# Codec_s.net
KiCad netlist of a schematic drawn in Altium Designer
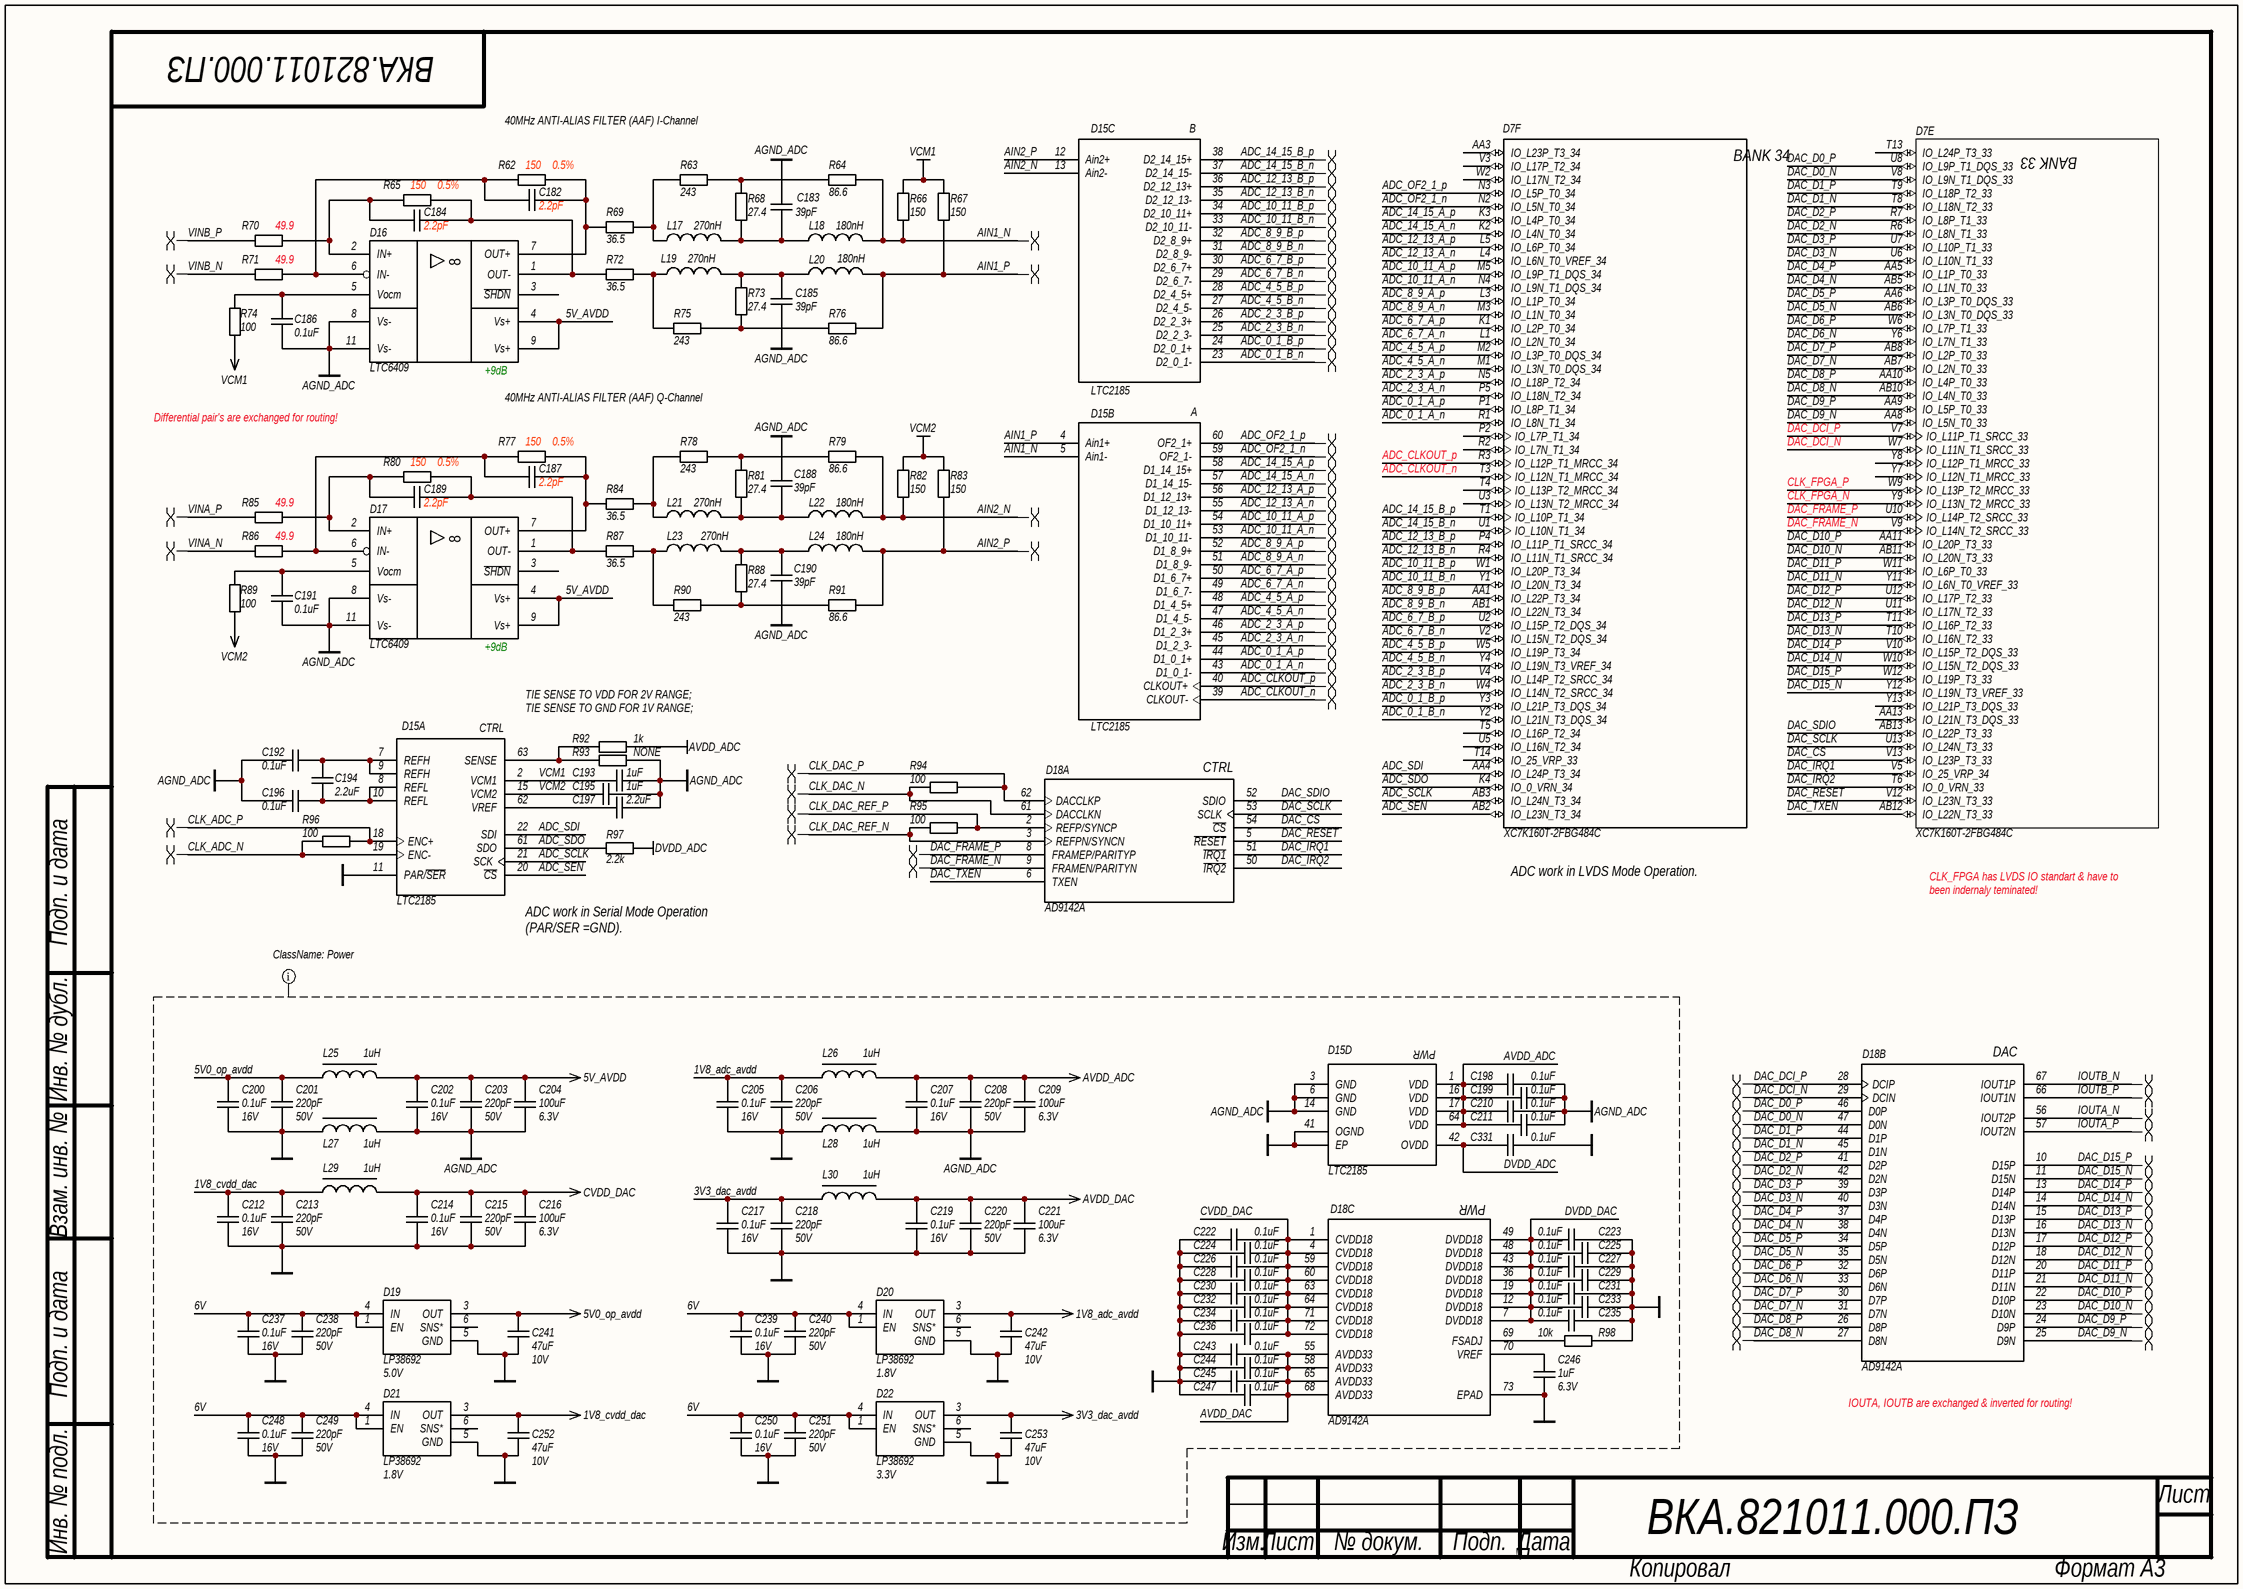
[diagram p0: Codec's.SchDoc]

(export (version "E")
  (design (tool "Eeschema 10.0.6"))
  (components
    (comp (ref "C182")
      (value "2.2pF")
      (footprint "C0402")
      (description "SMD Capacitor")
      (fields (field (name "MANUFACTURER") "Murata") (field (name "TOLERANCE") "0.1pF"))
      (libsource (lib "Kintex_SDR") (part "CAP"))
    )
    (comp (ref "C183")
      (value "39pF")
      (footprint "C0402")
      (description "SMD Capacitor")
      (fields (field (name "MANUFACTURER") "Murata") (field (name "TOLERANCE") "1%"))
      (libsource (lib "Kintex_SDR") (part "CAP"))
    )
    (comp (ref "C184")
      (value "2.2pF")
      (footprint "C0402")
      (description "SMD Capacitor")
      (fields (field (name "MANUFACTURER") "Murata") (field (name "TOLERANCE") "0.1pF"))
      (libsource (lib "Kintex_SDR") (part "CAP"))
    )
    (comp (ref "C185")
      (value "39pF")
      (footprint "C0402")
      (description "SMD Capacitor")
      (fields (field (name "MANUFACTURER") "Murata") (field (name "TOLERANCE") "1%"))
      (libsource (lib "Kintex_SDR") (part "CAP"))
    )
    (comp (ref "C186")
      (value "0.1uF")
      (footprint "C0402")
      (description "SMD Capacitor")
      (fields (field (name "MANUFACTURER") "Murata") (field (name "TOLERANCE") "10%"))
      (libsource (lib "Kintex_SDR") (part "CAP"))
    )
    (comp (ref "C187")
      (value "2.2pF")
      (footprint "C0402")
      (description "SMD Capacitor")
      (fields (field (name "MANUFACTURER") "Murata") (field (name "TOLERANCE") "0.1pF"))
      (libsource (lib "Kintex_SDR") (part "CAP"))
    )
    (comp (ref "C188")
      (value "39pF")
      (footprint "C0402")
      (description "SMD Capacitor")
      (fields (field (name "MANUFACTURER") "Murata") (field (name "TOLERANCE") "1%"))
      (libsource (lib "Kintex_SDR") (part "CAP"))
    )
    (comp (ref "C189")
      (value "2.2pF")
      (footprint "C0402")
      (description "SMD Capacitor")
      (fields (field (name "MANUFACTURER") "Murata") (field (name "TOLERANCE") "0.1pF"))
      (libsource (lib "Kintex_SDR") (part "CAP"))
    )
    (comp (ref "C190")
      (value "39pF")
      (footprint "C0402")
      (description "SMD Capacitor")
      (fields (field (name "MANUFACTURER") "Murata") (field (name "TOLERANCE") "1%"))
      (libsource (lib "Kintex_SDR") (part "CAP"))
    )
    (comp (ref "C191")
      (value "0.1uF")
      (footprint "C0402")
      (description "SMD Capacitor")
      (fields (field (name "MANUFACTURER") "Murata") (field (name "TOLERANCE") "10%"))
      (libsource (lib "Kintex_SDR") (part "CAP"))
    )
    (comp (ref "C192")
      (value "0.1uF")
      (footprint "C0402")
      (description "SMD Capacitor")
      (fields (field (name "MANUFACTURER") "Murata") (field (name "TOLERANCE") "10%"))
      (libsource (lib "Kintex_SDR") (part "CAP"))
    )
    (comp (ref "C193")
      (value "1uF")
      (footprint "C0402")
      (description "SMD Capacitor")
      (fields (field (name "MANUFACTURER") "Murata") (field (name "TOLERANCE") "10%"))
      (libsource (lib "Kintex_SDR") (part "CAP"))
    )
    (comp (ref "C194")
      (value "2.2uF")
      (footprint "C0603")
      (description "SMD Capacitor")
      (fields (field (name "MANUFACTURER") "Murata") (field (name "TOLERANCE") "10%"))
      (libsource (lib "Kintex_SDR") (part "CAP"))
    )
    (comp (ref "C195")
      (value "1uF")
      (footprint "C0402")
      (description "SMD Capacitor")
      (fields (field (name "MANUFACTURER") "Murata") (field (name "TOLERANCE") "10%"))
      (libsource (lib "Kintex_SDR") (part "CAP"))
    )
    (comp (ref "C196")
      (value "0.1uF")
      (footprint "C0402")
      (description "SMD Capacitor")
      (fields (field (name "MANUFACTURER") "Murata") (field (name "TOLERANCE") "10%"))
      (libsource (lib "Kintex_SDR") (part "CAP"))
    )
    (comp (ref "C197")
      (value "2.2uF")
      (footprint "C0603")
      (description "SMD Capacitor")
      (fields (field (name "MANUFACTURER") "Murata") (field (name "TOLERANCE") "10%"))
      (libsource (lib "Kintex_SDR") (part "CAP"))
    )
    (comp (ref "C198")
      (value "0.1uF")
      (footprint "C0402")
      (description "SMD Capacitor")
      (fields (field (name "MANUFACTURER") "Murata") (field (name "TOLERANCE") "10%"))
      (libsource (lib "Kintex_SDR") (part "CAP"))
    )
    (comp (ref "C199")
      (value "0.1uF")
      (footprint "C0402")
      (description "SMD Capacitor")
      (fields (field (name "MANUFACTURER") "Murata") (field (name "TOLERANCE") "10%"))
      (libsource (lib "Kintex_SDR") (part "CAP"))
    )
    (comp (ref "C200")
      (value "0.1uF")
      (footprint "C0603")
      (description "SMD Capacitor")
      (fields
        (field (name "MANUFACTURER") "Murata")
        (field (name "TOLERANCE") "10%")
        (field (name "VOLTAGE") "16V")
      )
      (libsource (lib "Kintex_SDR") (part "CAP"))
    )
    (comp (ref "C201")
      (value "220pF")
      (footprint "C0603")
      (description "SMD Capacitor")
      (fields
        (field (name "MANUFACTURER") "Murata")
        (field (name "TOLERANCE") "10%")
        (field (name "VOLTAGE") "50V")
      )
      (libsource (lib "Kintex_SDR") (part "CAP"))
    )
    (comp (ref "C202")
      (value "0.1uF")
      (footprint "C0603")
      (description "SMD Capacitor")
      (fields
        (field (name "MANUFACTURER") "Murata")
        (field (name "TOLERANCE") "10%")
        (field (name "VOLTAGE") "16V")
      )
      (libsource (lib "Kintex_SDR") (part "CAP"))
    )
    (comp (ref "C203")
      (value "220pF")
      (footprint "C0603")
      (description "SMD Capacitor")
      (fields
        (field (name "MANUFACTURER") "Murata")
        (field (name "TOLERANCE") "10%")
        (field (name "VOLTAGE") "50V")
      )
      (libsource (lib "Kintex_SDR") (part "CAP"))
    )
    (comp (ref "C204")
      (value "100uF")
      (footprint "C1210")
      (description "SMD Capacitor")
      (fields
        (field (name "MANUFACTURER") "Murata")
        (field (name "TOLERANCE") "20%")
        (field (name "VOLTAGE") "6.3V")
      )
      (libsource (lib "Kintex_SDR") (part "CAP uF"))
    )
    (comp (ref "C205")
      (value "0.1uF")
      (footprint "C0603")
      (description "SMD Capacitor")
      (fields
        (field (name "MANUFACTURER") "Murata")
        (field (name "TOLERANCE") "10%")
        (field (name "VOLTAGE") "16V")
      )
      (libsource (lib "Kintex_SDR") (part "CAP"))
    )
    (comp (ref "C206")
      (value "220pF")
      (footprint "C0603")
      (description "SMD Capacitor")
      (fields
        (field (name "MANUFACTURER") "Murata")
        (field (name "TOLERANCE") "10%")
        (field (name "VOLTAGE") "50V")
      )
      (libsource (lib "Kintex_SDR") (part "CAP"))
    )
    (comp (ref "C207")
      (value "0.1uF")
      (footprint "C0603")
      (description "SMD Capacitor")
      (fields
        (field (name "MANUFACTURER") "Murata")
        (field (name "TOLERANCE") "10%")
        (field (name "VOLTAGE") "16V")
      )
      (libsource (lib "Kintex_SDR") (part "CAP"))
    )
    (comp (ref "C208")
      (value "220pF")
      (footprint "C0603")
      (description "SMD Capacitor")
      (fields
        (field (name "MANUFACTURER") "Murata")
        (field (name "TOLERANCE") "10%")
        (field (name "VOLTAGE") "50V")
      )
      (libsource (lib "Kintex_SDR") (part "CAP"))
    )
    (comp (ref "C209")
      (value "100uF")
      (footprint "C1210")
      (description "SMD Capacitor")
      (fields
        (field (name "MANUFACTURER") "Murata")
        (field (name "TOLERANCE") "20%")
        (field (name "VOLTAGE") "6.3V")
      )
      (libsource (lib "Kintex_SDR") (part "CAP uF"))
    )
    (comp (ref "C210")
      (value "0.1uF")
      (footprint "C0402")
      (description "SMD Capacitor")
      (fields (field (name "MANUFACTURER") "Murata") (field (name "TOLERANCE") "10%"))
      (libsource (lib "Kintex_SDR") (part "CAP"))
    )
    (comp (ref "C211")
      (value "0.1uF")
      (footprint "C0402")
      (description "SMD Capacitor")
      (fields (field (name "MANUFACTURER") "Murata") (field (name "TOLERANCE") "10%"))
      (libsource (lib "Kintex_SDR") (part "CAP"))
    )
    (comp (ref "C212")
      (value "0.1uF")
      (footprint "C0603")
      (description "SMD Capacitor")
      (fields
        (field (name "MANUFACTURER") "Murata")
        (field (name "TOLERANCE") "10%")
        (field (name "VOLTAGE") "16V")
      )
      (libsource (lib "Kintex_SDR") (part "CAP"))
    )
    (comp (ref "C213")
      (value "220pF")
      (footprint "C0603")
      (description "SMD Capacitor")
      (fields
        (field (name "MANUFACTURER") "Murata")
        (field (name "TOLERANCE") "10%")
        (field (name "VOLTAGE") "50V")
      )
      (libsource (lib "Kintex_SDR") (part "CAP"))
    )
    (comp (ref "C214")
      (value "0.1uF")
      (footprint "C0603")
      (description "SMD Capacitor")
      (fields
        (field (name "MANUFACTURER") "Murata")
        (field (name "TOLERANCE") "10%")
        (field (name "VOLTAGE") "16V")
      )
      (libsource (lib "Kintex_SDR") (part "CAP"))
    )
    (comp (ref "C215")
      (value "220pF")
      (footprint "C0603")
      (description "SMD Capacitor")
      (fields
        (field (name "MANUFACTURER") "Murata")
        (field (name "TOLERANCE") "10%")
        (field (name "VOLTAGE") "50V")
      )
      (libsource (lib "Kintex_SDR") (part "CAP"))
    )
    (comp (ref "C216")
      (value "100uF")
      (footprint "C1210")
      (description "SMD Capacitor")
      (fields
        (field (name "MANUFACTURER") "Murata")
        (field (name "TOLERANCE") "20%")
        (field (name "VOLTAGE") "6.3V")
      )
      (libsource (lib "Kintex_SDR") (part "CAP uF"))
    )
    (comp (ref "C217")
      (value "0.1uF")
      (footprint "C0603")
      (description "SMD Capacitor")
      (fields
        (field (name "MANUFACTURER") "Murata")
        (field (name "TOLERANCE") "10%")
        (field (name "VOLTAGE") "16V")
      )
      (libsource (lib "Kintex_SDR") (part "CAP"))
    )
    (comp (ref "C218")
      (value "220pF")
      (footprint "C0603")
      (description "SMD Capacitor")
      (fields
        (field (name "MANUFACTURER") "Murata")
        (field (name "TOLERANCE") "10%")
        (field (name "VOLTAGE") "50V")
      )
      (libsource (lib "Kintex_SDR") (part "CAP"))
    )
    (comp (ref "C219")
      (value "0.1uF")
      (footprint "C0603")
      (description "SMD Capacitor")
      (fields
        (field (name "MANUFACTURER") "Murata")
        (field (name "TOLERANCE") "10%")
        (field (name "VOLTAGE") "16V")
      )
      (libsource (lib "Kintex_SDR") (part "CAP"))
    )
    (comp (ref "C220")
      (value "220pF")
      (footprint "C0603")
      (description "SMD Capacitor")
      (fields
        (field (name "MANUFACTURER") "Murata")
        (field (name "TOLERANCE") "10%")
        (field (name "VOLTAGE") "50V")
      )
      (libsource (lib "Kintex_SDR") (part "CAP"))
    )
    (comp (ref "C221")
      (value "100uF")
      (footprint "C1210")
      (description "SMD Capacitor")
      (fields
        (field (name "MANUFACTURER") "Murata")
        (field (name "TOLERANCE") "20%")
        (field (name "VOLTAGE") "6.3V")
      )
      (libsource (lib "Kintex_SDR") (part "CAP uF"))
    )
    (comp (ref "C222")
      (value "0.1uF")
      (footprint "C0402")
      (description "SMD Capacitor")
      (fields (field (name "MANUFACTURER") "Murata") (field (name "TOLERANCE") "10%"))
      (libsource (lib "Kintex_SDR") (part "CAP"))
    )
    (comp (ref "C223")
      (value "0.1uF")
      (footprint "C0402")
      (description "SMD Capacitor")
      (fields (field (name "MANUFACTURER") "Murata") (field (name "TOLERANCE") "10%"))
      (libsource (lib "Kintex_SDR") (part "CAP"))
    )
    (comp (ref "C224")
      (value "0.1uF")
      (footprint "C0402")
      (description "SMD Capacitor")
      (fields (field (name "MANUFACTURER") "Murata") (field (name "TOLERANCE") "10%"))
      (libsource (lib "Kintex_SDR") (part "CAP"))
    )
    (comp (ref "C225")
      (value "0.1uF")
      (footprint "C0402")
      (description "SMD Capacitor")
      (fields (field (name "MANUFACTURER") "Murata") (field (name "TOLERANCE") "10%"))
      (libsource (lib "Kintex_SDR") (part "CAP"))
    )
    (comp (ref "C226")
      (value "0.1uF")
      (footprint "C0402")
      (description "SMD Capacitor")
      (fields (field (name "MANUFACTURER") "Murata") (field (name "TOLERANCE") "10%"))
      (libsource (lib "Kintex_SDR") (part "CAP"))
    )
    (comp (ref "C227")
      (value "0.1uF")
      (footprint "C0402")
      (description "SMD Capacitor")
      (fields (field (name "MANUFACTURER") "Murata") (field (name "TOLERANCE") "10%"))
      (libsource (lib "Kintex_SDR") (part "CAP"))
    )
    (comp (ref "C228")
      (value "0.1uF")
      (footprint "C0402")
      (description "SMD Capacitor")
      (fields (field (name "MANUFACTURER") "Murata") (field (name "TOLERANCE") "10%"))
      (libsource (lib "Kintex_SDR") (part "CAP"))
    )
    (comp (ref "C229")
      (value "0.1uF")
      (footprint "C0402")
      (description "SMD Capacitor")
      (fields (field (name "MANUFACTURER") "Murata") (field (name "TOLERANCE") "10%"))
      (libsource (lib "Kintex_SDR") (part "CAP"))
    )
    (comp (ref "C230")
      (value "0.1uF")
      (footprint "C0402")
      (description "SMD Capacitor")
      (fields (field (name "MANUFACTURER") "Murata") (field (name "TOLERANCE") "10%"))
      (libsource (lib "Kintex_SDR") (part "CAP"))
    )
    (comp (ref "C231")
      (value "0.1uF")
      (footprint "C0402")
      (description "SMD Capacitor")
      (fields (field (name "MANUFACTURER") "Murata") (field (name "TOLERANCE") "10%"))
      (libsource (lib "Kintex_SDR") (part "CAP"))
    )
    (comp (ref "C232")
      (value "0.1uF")
      (footprint "C0402")
      (description "SMD Capacitor")
      (fields (field (name "MANUFACTURER") "Murata") (field (name "TOLERANCE") "10%"))
      (libsource (lib "Kintex_SDR") (part "CAP"))
    )
    (comp (ref "C233")
      (value "0.1uF")
      (footprint "C0402")
      (description "SMD Capacitor")
      (fields (field (name "MANUFACTURER") "Murata") (field (name "TOLERANCE") "10%"))
      (libsource (lib "Kintex_SDR") (part "CAP"))
    )
    (comp (ref "C234")
      (value "0.1uF")
      (footprint "C0402")
      (description "SMD Capacitor")
      (fields (field (name "MANUFACTURER") "Murata") (field (name "TOLERANCE") "10%"))
      (libsource (lib "Kintex_SDR") (part "CAP"))
    )
    (comp (ref "C235")
      (value "0.1uF")
      (footprint "C0402")
      (description "SMD Capacitor")
      (fields (field (name "MANUFACTURER") "Murata") (field (name "TOLERANCE") "10%"))
      (libsource (lib "Kintex_SDR") (part "CAP"))
    )
    (comp (ref "C236")
      (value "0.1uF")
      (footprint "C0402")
      (description "SMD Capacitor")
      (fields (field (name "MANUFACTURER") "Murata") (field (name "TOLERANCE") "10%"))
      (libsource (lib "Kintex_SDR") (part "CAP"))
    )
    (comp (ref "C237")
      (value "0.1uF")
      (footprint "C0603")
      (description "SMD Capacitor")
      (fields
        (field (name "MANUFACTURER") "Murata")
        (field (name "TOLERANCE") "10%")
        (field (name "VOLTAGE") "16V")
      )
      (libsource (lib "Kintex_SDR") (part "CAP"))
    )
    (comp (ref "C238")
      (value "220pF")
      (footprint "C0603")
      (description "SMD Capacitor")
      (fields
        (field (name "MANUFACTURER") "Murata")
        (field (name "TOLERANCE") "10%")
        (field (name "VOLTAGE") "50V")
      )
      (libsource (lib "Kintex_SDR") (part "CAP"))
    )
    (comp (ref "C239")
      (value "0.1uF")
      (footprint "C0603")
      (description "SMD Capacitor")
      (fields
        (field (name "MANUFACTURER") "Murata")
        (field (name "TOLERANCE") "10%")
        (field (name "VOLTAGE") "16V")
      )
      (libsource (lib "Kintex_SDR") (part "CAP"))
    )
    (comp (ref "C240")
      (value "220pF")
      (footprint "C0603")
      (description "SMD Capacitor")
      (fields
        (field (name "MANUFACTURER") "Murata")
        (field (name "TOLERANCE") "10%")
        (field (name "VOLTAGE") "50V")
      )
      (libsource (lib "Kintex_SDR") (part "CAP"))
    )
    (comp (ref "C241")
      (value "47uF")
      (footprint "C1210")
      (description "SMD Capacitor")
      (fields
        (field (name "MANUFACTURER") "Murata")
        (field (name "TOLERANCE") "10%")
        (field (name "VOLTAGE") "10V")
      )
      (libsource (lib "Kintex_SDR") (part "CAP uF"))
    )
    (comp (ref "C242")
      (value "47uF")
      (footprint "C1210")
      (description "SMD Capacitor")
      (fields
        (field (name "MANUFACTURER") "Murata")
        (field (name "TOLERANCE") "10%")
        (field (name "VOLTAGE") "10V")
      )
      (libsource (lib "Kintex_SDR") (part "CAP uF"))
    )
    (comp (ref "C243")
      (value "0.1uF")
      (footprint "C0402")
      (description "SMD Capacitor")
      (fields (field (name "MANUFACTURER") "Murata") (field (name "TOLERANCE") "10%"))
      (libsource (lib "Kintex_SDR") (part "CAP"))
    )
    (comp (ref "C244")
      (value "0.1uF")
      (footprint "C0402")
      (description "SMD Capacitor")
      (fields (field (name "MANUFACTURER") "Murata") (field (name "TOLERANCE") "10%"))
      (libsource (lib "Kintex_SDR") (part "CAP"))
    )
    (comp (ref "C245")
      (value "0.1uF")
      (footprint "C0402")
      (description "SMD Capacitor")
      (fields (field (name "MANUFACTURER") "Murata") (field (name "TOLERANCE") "10%"))
      (libsource (lib "Kintex_SDR") (part "CAP"))
    )
    (comp (ref "C246")
      (value "1uF")
      (footprint "C0402")
      (description "SMD Capacitor")
      (fields
        (field (name "MANUFACTURER") "Murata")
        (field (name "TOLERANCE") "10%")
        (field (name "VOLTAGE") "6.3V")
      )
      (libsource (lib "Kintex_SDR") (part "CAP"))
    )
    (comp (ref "C247")
      (value "0.1uF")
      (footprint "C0402")
      (description "SMD Capacitor")
      (fields (field (name "MANUFACTURER") "Murata") (field (name "TOLERANCE") "10%"))
      (libsource (lib "Kintex_SDR") (part "CAP"))
    )
    (comp (ref "C248")
      (value "0.1uF")
      (footprint "C0603")
      (description "SMD Capacitor")
      (fields
        (field (name "MANUFACTURER") "Murata")
        (field (name "TOLERANCE") "10%")
        (field (name "VOLTAGE") "16V")
      )
      (libsource (lib "Kintex_SDR") (part "CAP"))
    )
    (comp (ref "C249")
      (value "220pF")
      (footprint "C0603")
      (description "SMD Capacitor")
      (fields
        (field (name "MANUFACTURER") "Murata")
        (field (name "TOLERANCE") "10%")
        (field (name "VOLTAGE") "50V")
      )
      (libsource (lib "Kintex_SDR") (part "CAP"))
    )
    (comp (ref "C250")
      (value "0.1uF")
      (footprint "C0603")
      (description "SMD Capacitor")
      (fields
        (field (name "MANUFACTURER") "Murata")
        (field (name "TOLERANCE") "10%")
        (field (name "VOLTAGE") "16V")
      )
      (libsource (lib "Kintex_SDR") (part "CAP"))
    )
    (comp (ref "C251")
      (value "220pF")
      (footprint "C0603")
      (description "SMD Capacitor")
      (fields
        (field (name "MANUFACTURER") "Murata")
        (field (name "TOLERANCE") "10%")
        (field (name "VOLTAGE") "50V")
      )
      (libsource (lib "Kintex_SDR") (part "CAP"))
    )
    (comp (ref "C252")
      (value "47uF")
      (footprint "C1210")
      (description "SMD Capacitor")
      (fields
        (field (name "MANUFACTURER") "Murata")
        (field (name "TOLERANCE") "10%")
        (field (name "VOLTAGE") "10V")
      )
      (libsource (lib "Kintex_SDR") (part "CAP uF"))
    )
    (comp (ref "C253")
      (value "47uF")
      (footprint "C1210")
      (description "SMD Capacitor")
      (fields
        (field (name "MANUFACTURER") "Murata")
        (field (name "TOLERANCE") "10%")
        (field (name "VOLTAGE") "10V")
      )
      (libsource (lib "Kintex_SDR") (part "CAP uF"))
    )
    (comp (ref "C331")
      (value "0.1uF")
      (footprint "C0402")
      (description "SMD Capacitor")
      (fields (field (name "MANUFACTURER") "Murata") (field (name "TOLERANCE") "10%"))
      (libsource (lib "Kintex_SDR") (part "CAP"))
    )
    (comp (ref "D7")
      (value "XC7K160T-2FBG484C")
      (footprint "FBG484")
      (description "Xilinx 7-Series FPGA")
      (fields (field (name "MANUFACTURER") "Xilinx"))
      (libsource (lib "Kintex_SDR") (part "XC7K160T-2FBG484C"))
    )
    (comp (ref "D15")
      (value "LTC2185")
      (footprint "QFN-64")
      (description "Dual 16-Bit, 125Msps  Low Power 3V ADC")
      (fields (field (name "VOLTAGE") "Single 1.8V Supply"))
      (libsource (lib "Kintex_SDR") (part "LTC2185"))
    )
    (comp (ref "D16")
      (value "LTC6409")
      (footprint "QFN-10")
      (description "Differential Amplifier/ADC   Driver")
      (fields (field (name "MANUFACTURER") "Linear Technology") (field (name "VOLTAGE") "2.7V to 5.25V"))
      (libsource (lib "Kintex_SDR") (part "LTC6409"))
    )
    (comp (ref "D17")
      (value "LTC6409")
      (footprint "QFN-10")
      (description "Differential Amplifier/ADC   Driver")
      (fields (field (name "MANUFACTURER") "Linear Technology") (field (name "VOLTAGE") "2.7V to 5.25V"))
      (libsource (lib "Kintex_SDR") (part "LTC6409"))
    )
    (comp (ref "D18")
      (value "AD9142A")
      (footprint "LFCSP_VQ-72")
      (description "Dual, 16-Bit, 1600 MSPS, TxDAC+   Digital-to-Analog Converter")
      (fields (field (name "VOLTAGE") "3.3V, 1.8V"))
      (libsource (lib "Kintex_SDR") (part "AD9142A"))
    )
    (comp (ref "D19")
      (value "LP38692")
      (footprint "SOT-223-5")
      (description "Linear Regulator")
      (fields (field (name "VOLTAGE") "5.0V"))
      (libsource (lib "Kintex_SDR") (part "LP38692"))
    )
    (comp (ref "D20")
      (value "LP38692")
      (footprint "SOT-223-5")
      (description "Linear Regulator")
      (fields (field (name "VOLTAGE") "1.8V"))
      (libsource (lib "Kintex_SDR") (part "LP38692"))
    )
    (comp (ref "D21")
      (value "LP38692")
      (footprint "SOT-223-5")
      (description "Linear Regulator")
      (fields (field (name "VOLTAGE") "1.8V"))
      (libsource (lib "Kintex_SDR") (part "LP38692"))
    )
    (comp (ref "D22")
      (value "LP38692")
      (footprint "SOT-223-5")
      (description "Linear Regulator")
      (fields (field (name "VOLTAGE") "3.3V"))
      (libsource (lib "Kintex_SDR") (part "LP38692"))
    )
    (comp (ref "L17")
      (value "270nH")
      (footprint "L0603")
      (description "Chip SMD Inductor")
      (fields (field (name "MANUFACTURER") "Murata") (field (name "TOLERANCE") "±2%"))
      (libsource (lib "Kintex_SDR") (part "Inductor RF"))
    )
    (comp (ref "L18")
      (value "180nH")
      (footprint "L0603")
      (description "Chip SMD Inductor")
      (fields (field (name "MANUFACTURER") "Murata") (field (name "TOLERANCE") "±2%"))
      (libsource (lib "Kintex_SDR") (part "Inductor RF"))
    )
    (comp (ref "L19")
      (value "270nH")
      (footprint "L0603")
      (description "Chip SMD Inductor")
      (fields (field (name "MANUFACTURER") "Murata") (field (name "TOLERANCE") "±2%"))
      (libsource (lib "Kintex_SDR") (part "Inductor RF"))
    )
    (comp (ref "L20")
      (value "180nH")
      (footprint "L0603")
      (description "Chip SMD Inductor")
      (fields (field (name "MANUFACTURER") "Murata") (field (name "TOLERANCE") "±2%"))
      (libsource (lib "Kintex_SDR") (part "Inductor RF"))
    )
    (comp (ref "L21")
      (value "270nH")
      (footprint "L0603")
      (description "Chip SMD Inductor")
      (fields (field (name "MANUFACTURER") "Murata") (field (name "TOLERANCE") "±2%"))
      (libsource (lib "Kintex_SDR") (part "Inductor RF"))
    )
    (comp (ref "L22")
      (value "180nH")
      (footprint "L0603")
      (description "Chip SMD Inductor")
      (fields (field (name "MANUFACTURER") "Murata") (field (name "TOLERANCE") "±2%"))
      (libsource (lib "Kintex_SDR") (part "Inductor RF"))
    )
    (comp (ref "L23")
      (value "270nH")
      (footprint "L0603")
      (description "Chip SMD Inductor")
      (fields (field (name "MANUFACTURER") "Murata") (field (name "TOLERANCE") "±2%"))
      (libsource (lib "Kintex_SDR") (part "Inductor RF"))
    )
    (comp (ref "L24")
      (value "180nH")
      (footprint "L0603")
      (description "Chip SMD Inductor")
      (fields (field (name "MANUFACTURER") "Murata") (field (name "TOLERANCE") "±2%"))
      (libsource (lib "Kintex_SDR") (part "Inductor RF"))
    )
    (comp (ref "L25")
      (value "1uH")
      (footprint "L1210_Murata")
      (description "Inductor Power Lines")
      (fields (field (name "MANUFACTURER") "Murata") (field (name "TOLERANCE") "5%"))
      (libsource (lib "Kintex_SDR") (part "Inductor LF"))
    )
    (comp (ref "L26")
      (value "1uH")
      (footprint "L1210_Murata")
      (description "Inductor Power Lines")
      (fields (field (name "MANUFACTURER") "Murata") (field (name "TOLERANCE") "5%"))
      (libsource (lib "Kintex_SDR") (part "Inductor LF"))
    )
    (comp (ref "L27")
      (value "1uH")
      (footprint "L1210_Murata")
      (description "Inductor Power Lines")
      (fields (field (name "MANUFACTURER") "Murata") (field (name "TOLERANCE") "5%"))
      (libsource (lib "Kintex_SDR") (part "Inductor LF"))
    )
    (comp (ref "L28")
      (value "1uH")
      (footprint "L1210_Murata")
      (description "Inductor Power Lines")
      (fields (field (name "MANUFACTURER") "Murata") (field (name "TOLERANCE") "5%"))
      (libsource (lib "Kintex_SDR") (part "Inductor LF"))
    )
    (comp (ref "L29")
      (value "1uH")
      (footprint "L1210_Murata")
      (description "Inductor Power Lines")
      (fields (field (name "MANUFACTURER") "Murata") (field (name "TOLERANCE") "5%"))
      (libsource (lib "Kintex_SDR") (part "Inductor LF"))
    )
    (comp (ref "L30")
      (value "1uH")
      (footprint "L1210_Murata")
      (description "Inductor Power Lines")
      (fields (field (name "MANUFACTURER") "Murata") (field (name "TOLERANCE") "5%"))
      (libsource (lib "Kintex_SDR") (part "Inductor LF"))
    )
    (comp (ref "R62")
      (value "150")
      (footprint "R0402")
      (description "SMD Resistor")
      (fields
        (field (name "POWER") "0.062 Wt")
        (field (name "TOLERANCE") "0.5%")
        (field (name "MANUFACTURER") "Panasonic Electronic Components")
      )
      (libsource (lib "Kintex_SDR") (part "RES"))
    )
    (comp (ref "R63")
      (value "243")
      (footprint "R0402")
      (description "SMD Resistor")
      (fields (field (name "POWER") "0.062 Wt") (field (name "TOLERANCE") "1%"))
      (libsource (lib "Kintex_SDR") (part "RES"))
    )
    (comp (ref "R64")
      (value "86.6")
      (footprint "R0402")
      (description "SMD Resistor")
      (fields (field (name "POWER") "0.062 Wt") (field (name "TOLERANCE") "1%"))
      (libsource (lib "Kintex_SDR") (part "RES"))
    )
    (comp (ref "R65")
      (value "150")
      (footprint "R0402")
      (description "SMD Resistor")
      (fields
        (field (name "POWER") "0.062 Wt")
        (field (name "TOLERANCE") "0.5%")
        (field (name "MANUFACTURER") "Panasonic Electronic Components")
      )
      (libsource (lib "Kintex_SDR") (part "RES"))
    )
    (comp (ref "R66")
      (value "150")
      (footprint "R0402")
      (description "SMD Resistor")
      (fields (field (name "POWER") "0.062 Wt") (field (name "TOLERANCE") "1%"))
      (libsource (lib "Kintex_SDR") (part "RES"))
    )
    (comp (ref "R67")
      (value "150")
      (footprint "R0402")
      (description "SMD Resistor")
      (fields (field (name "POWER") "0.062 Wt") (field (name "TOLERANCE") "1%"))
      (libsource (lib "") (part "RES_1"))
    )
    (comp (ref "R68")
      (value "27.4")
      (footprint "R0402")
      (description "SMD Resistor")
      (fields (field (name "POWER") "0.062 Wt") (field (name "TOLERANCE") "1%"))
      (libsource (lib "") (part "RES_2"))
    )
    (comp (ref "R69")
      (value "36.5")
      (footprint "R0402")
      (description "SMD Resistor")
      (fields (field (name "POWER") "0.062 Wt") (field (name "TOLERANCE") "1%"))
      (libsource (lib "") (part "RES_1"))
    )
    (comp (ref "R70")
      (value "49.9")
      (footprint "R0402")
      (description "SMD Resistor")
      (fields (field (name "POWER") "0.063 Wt") (field (name "TOLERANCE") "0.5%"))
      (libsource (lib "") (part "RES_1"))
    )
    (comp (ref "R71")
      (value "49.9")
      (footprint "R0402")
      (description "SMD Resistor")
      (fields (field (name "POWER") "0.063 Wt") (field (name "TOLERANCE") "0.5%"))
      (libsource (lib "") (part "RES_1"))
    )
    (comp (ref "R72")
      (value "36.5")
      (footprint "R0402")
      (description "SMD Resistor")
      (fields (field (name "POWER") "0.062 Wt") (field (name "TOLERANCE") "1%"))
      (libsource (lib "") (part "RES_1"))
    )
    (comp (ref "R73")
      (value "27.4")
      (footprint "R0402")
      (description "SMD Resistor")
      (fields (field (name "POWER") "0.062 Wt") (field (name "TOLERANCE") "1%"))
      (libsource (lib "") (part "RES_2"))
    )
    (comp (ref "R74")
      (value "100")
      (footprint "R0402")
      (description "SMD Resistor")
      (fields (field (name "POWER") "0.062 Wt") (field (name "TOLERANCE") "5%"))
      (libsource (lib "") (part "RES_1"))
    )
    (comp (ref "R75")
      (value "243")
      (footprint "R0402")
      (description "SMD Resistor")
      (fields (field (name "POWER") "0.062 Wt") (field (name "TOLERANCE") "1%"))
      (libsource (lib "Kintex_SDR") (part "RES"))
    )
    (comp (ref "R76")
      (value "86.6")
      (footprint "R0402")
      (description "SMD Resistor")
      (fields (field (name "POWER") "0.062 Wt") (field (name "TOLERANCE") "1%"))
      (libsource (lib "Kintex_SDR") (part "RES"))
    )
    (comp (ref "R77")
      (value "150")
      (footprint "R0402")
      (description "SMD Resistor")
      (fields
        (field (name "POWER") "0.062 Wt")
        (field (name "TOLERANCE") "0.5%")
        (field (name "MANUFACTURER") "Panasonic Electronic Components")
      )
      (libsource (lib "Kintex_SDR") (part "RES"))
    )
    (comp (ref "R78")
      (value "243")
      (footprint "R0402")
      (description "SMD Resistor")
      (fields (field (name "POWER") "0.062 Wt") (field (name "TOLERANCE") "1%"))
      (libsource (lib "Kintex_SDR") (part "RES"))
    )
    (comp (ref "R79")
      (value "86.6")
      (footprint "R0402")
      (description "SMD Resistor")
      (fields (field (name "POWER") "0.062 Wt") (field (name "TOLERANCE") "1%"))
      (libsource (lib "Kintex_SDR") (part "RES"))
    )
    (comp (ref "R80")
      (value "150")
      (footprint "R0402")
      (description "SMD Resistor")
      (fields
        (field (name "POWER") "0.062 Wt")
        (field (name "TOLERANCE") "0.5%")
        (field (name "MANUFACTURER") "Panasonic Electronic Components")
      )
      (libsource (lib "Kintex_SDR") (part "RES"))
    )
    (comp (ref "R81")
      (value "27.4")
      (footprint "R0402")
      (description "SMD Resistor")
      (fields (field (name "POWER") "0.062 Wt") (field (name "TOLERANCE") "1%"))
      (libsource (lib "") (part "RES_2"))
    )
    (comp (ref "R82")
      (value "150")
      (footprint "R0402")
      (description "SMD Resistor")
      (fields (field (name "POWER") "0.062 Wt") (field (name "TOLERANCE") "1%"))
      (libsource (lib "") (part "RES_2"))
    )
    (comp (ref "R83")
      (value "150")
      (footprint "R0402")
      (description "SMD Resistor")
      (fields (field (name "POWER") "0.062 Wt") (field (name "TOLERANCE") "1%"))
      (libsource (lib "") (part "RES_2"))
    )
    (comp (ref "R84")
      (value "36.5")
      (footprint "R0402")
      (description "SMD Resistor")
      (fields (field (name "POWER") "0.062 Wt") (field (name "TOLERANCE") "1%"))
      (libsource (lib "") (part "RES_1"))
    )
    (comp (ref "R85")
      (value "49.9")
      (footprint "R0402")
      (description "SMD Resistor")
      (fields (field (name "POWER") "0.063 Wt") (field (name "TOLERANCE") "0.5%"))
      (libsource (lib "") (part "RES_1"))
    )
    (comp (ref "R86")
      (value "49.9")
      (footprint "R0402")
      (description "SMD Resistor")
      (fields (field (name "POWER") "0.063 Wt") (field (name "TOLERANCE") "0.5%"))
      (libsource (lib "") (part "RES_1"))
    )
    (comp (ref "R87")
      (value "36.5")
      (footprint "R0402")
      (description "SMD Resistor")
      (fields (field (name "POWER") "0.062 Wt") (field (name "TOLERANCE") "1%"))
      (libsource (lib "") (part "RES_1"))
    )
    (comp (ref "R88")
      (value "27.4")
      (footprint "R0402")
      (description "SMD Resistor")
      (fields (field (name "POWER") "0.062 Wt") (field (name "TOLERANCE") "1%"))
      (libsource (lib "") (part "RES_2"))
    )
    (comp (ref "R89")
      (value "100")
      (footprint "R0402")
      (description "SMD Resistor")
      (fields (field (name "POWER") "0.062 Wt") (field (name "TOLERANCE") "5%"))
      (libsource (lib "") (part "RES_1"))
    )
    (comp (ref "R90")
      (value "243")
      (footprint "R0402")
      (description "SMD Resistor")
      (fields (field (name "POWER") "0.062 Wt") (field (name "TOLERANCE") "1%"))
      (libsource (lib "Kintex_SDR") (part "RES"))
    )
    (comp (ref "R91")
      (value "86.6")
      (footprint "R0402")
      (description "SMD Resistor")
      (fields (field (name "POWER") "0.062 Wt") (field (name "TOLERANCE") "1%"))
      (libsource (lib "Kintex_SDR") (part "RES"))
    )
    (comp (ref "R92")
      (value "1k")
      (footprint "R0402")
      (description "SMD Resistor")
      (fields (field (name "POWER") "0.062 Wt") (field (name "TOLERANCE") "5%"))
      (libsource (lib "Kintex_SDR") (part "RES"))
    )
    (comp (ref "R93")
      (value "NONE")
      (footprint "R0402")
      (description "SMD Resistor")
      (fields
        (field (name "POWER") "0.062 Wt")
        (field (name "MANUFACTURER") "Panasonic Electronic Components")
      )
      (libsource (lib "Kintex_SDR") (part "RES"))
    )
    (comp (ref "R94")
      (value "100")
      (footprint "R0402")
      (description "SMD Resistor")
      (fields (field (name "POWER") "0.062 Wt") (field (name "TOLERANCE") "5%"))
      (libsource (lib "Kintex_SDR") (part "RES"))
    )
    (comp (ref "R95")
      (value "100")
      (footprint "R0402")
      (description "SMD Resistor")
      (fields (field (name "POWER") "0.062 Wt") (field (name "TOLERANCE") "5%"))
      (libsource (lib "Kintex_SDR") (part "RES"))
    )
    (comp (ref "R96")
      (value "100")
      (footprint "R0402")
      (description "SMD Resistor")
      (fields (field (name "POWER") "0.062 Wt") (field (name "TOLERANCE") "5%"))
      (libsource (lib "Kintex_SDR") (part "RES"))
    )
    (comp (ref "R97")
      (value "2.2k")
      (footprint "R0402")
      (description "SMD Resistor")
      (fields (field (name "POWER") "0.062 Wt") (field (name "TOLERANCE") "5%"))
      (libsource (lib "") (part "RES_1"))
    )
    (comp (ref "R98")
      (value "10k")
      (footprint "R0402")
      (description "SMD Resistor")
      (fields (field (name "POWER") "0.062 Wt") (field (name "TOLERANCE") "5%"))
      (libsource (lib "Kintex_SDR") (part "RES"))
    )
  )
  (nets
    (net (code "1") (name "/6V") (class "Default")
      (node (ref "C237") (pin "2") (pinfunction "2_2") (pintype "passive"))
      (node (ref "C238") (pin "2") (pinfunction "2_2") (pintype "passive"))
      (node (ref "C239") (pin "2") (pinfunction "2_2") (pintype "passive"))
      (node (ref "C240") (pin "2") (pinfunction "2_2") (pintype "passive"))
      (node (ref "C248") (pin "2") (pinfunction "2_2") (pintype "passive"))
      (node (ref "C249") (pin "2") (pinfunction "2_2") (pintype "passive"))
      (node (ref "C250") (pin "2") (pinfunction "2_2") (pintype "passive"))
      (node (ref "C251") (pin "2") (pinfunction "2_2") (pintype "passive"))
      (node (ref "D19") (pin "1") (pinfunction "EN_1") (pintype "passive"))
      (node (ref "D19") (pin "4") (pinfunction "IN_4") (pintype "passive"))
      (node (ref "D20") (pin "1") (pinfunction "EN_1") (pintype "passive"))
      (node (ref "D20") (pin "4") (pinfunction "IN_4") (pintype "passive"))
      (node (ref "D21") (pin "1") (pinfunction "EN_1") (pintype "passive"))
      (node (ref "D21") (pin "4") (pinfunction "IN_4") (pintype "passive"))
      (node (ref "D22") (pin "1") (pinfunction "EN_1") (pintype "passive"))
      (node (ref "D22") (pin "4") (pinfunction "IN_4") (pintype "passive"))
    )
    (net (code "2") (name "/ADC_0_1_A_n") (class "Default")
      (node (ref "D15") (pin "43") (pinfunction "D1_0_1-_43") (pintype "passive"))
      (node (ref "D7") (pin "R1") (pinfunction "IO_L8N_T1_34_R1") (pintype "bidirectional"))
    )
    (net (code "3") (name "/ADC_0_1_A_p") (class "Default")
      (node (ref "D15") (pin "44") (pinfunction "D1_0_1+_44") (pintype "passive"))
      (node (ref "D7") (pin "P1") (pinfunction "IO_L8P_T1_34_P1") (pintype "bidirectional"))
    )
    (net (code "4") (name "/ADC_0_1_B_n") (class "Default")
      (node (ref "D15") (pin "23") (pinfunction "D2_0_1-_23") (pintype "passive"))
      (node (ref "D7") (pin "Y2") (pinfunction "IO_L21N_T3_DQS_34_Y2") (pintype "bidirectional"))
    )
    (net (code "5") (name "/ADC_0_1_B_p") (class "Default")
      (node (ref "D15") (pin "24") (pinfunction "D2_0_1+_24") (pintype "passive"))
      (node (ref "D7") (pin "Y3") (pinfunction "IO_L21P_T3_DQS_34_Y3") (pintype "bidirectional"))
    )
    (net (code "6") (name "/ADC_2_3_A_n") (class "Default")
      (node (ref "D15") (pin "45") (pinfunction "D1_2_3-_45") (pintype "passive"))
      (node (ref "D7") (pin "P5") (pinfunction "IO_L18N_T2_34_P5") (pintype "bidirectional"))
    )
    (net (code "7") (name "/ADC_2_3_A_p") (class "Default")
      (node (ref "D15") (pin "46") (pinfunction "D1_2_3+_46") (pintype "passive"))
      (node (ref "D7") (pin "N5") (pinfunction "IO_L18P_T2_34_N5") (pintype "bidirectional"))
    )
    (net (code "8") (name "/ADC_2_3_B_n") (class "Default")
      (node (ref "D15") (pin "25") (pinfunction "D2_2_3-_25") (pintype "passive"))
      (node (ref "D7") (pin "W4") (pinfunction "IO_L14N_T2_SRCC_34_W4") (pintype "bidirectional"))
    )
    (net (code "9") (name "/ADC_2_3_B_p") (class "Default")
      (node (ref "D15") (pin "26") (pinfunction "D2_2_3+_26") (pintype "passive"))
      (node (ref "D7") (pin "V4") (pinfunction "IO_L14P_T2_SRCC_34_V4") (pintype "bidirectional"))
    )
    (net (code "10") (name "/ADC_4_5_A_n") (class "Default")
      (node (ref "D15") (pin "47") (pinfunction "D1_4_5-_47") (pintype "passive"))
      (node (ref "D7") (pin "M1") (pinfunction "IO_L3N_T0_DQS_34_M1") (pintype "bidirectional"))
    )
    (net (code "11") (name "/ADC_4_5_A_p") (class "Default")
      (node (ref "D15") (pin "48") (pinfunction "D1_4_5+_48") (pintype "passive"))
      (node (ref "D7") (pin "M2") (pinfunction "IO_L3P_T0_DQS_34_M2") (pintype "bidirectional"))
    )
    (net (code "12") (name "/ADC_4_5_B_n") (class "Default")
      (node (ref "D15") (pin "27") (pinfunction "D2_4_5-_27") (pintype "passive"))
      (node (ref "D7") (pin "Y4") (pinfunction "IO_L19N_T3_VREF_34_Y4") (pintype "bidirectional"))
    )
    (net (code "13") (name "/ADC_4_5_B_p") (class "Default")
      (node (ref "D15") (pin "28") (pinfunction "D2_4_5+_28") (pintype "passive"))
      (node (ref "D7") (pin "W5") (pinfunction "IO_L19P_T3_34_W5") (pintype "bidirectional"))
    )
    (net (code "14") (name "/ADC_6_7_A_n") (class "Default")
      (node (ref "D15") (pin "49") (pinfunction "D1_6_7-_49") (pintype "passive"))
      (node (ref "D7") (pin "L1") (pinfunction "IO_L2N_T0_34_L1") (pintype "bidirectional"))
    )
    (net (code "15") (name "/ADC_6_7_A_p") (class "Default")
      (node (ref "D15") (pin "50") (pinfunction "D1_6_7+_50") (pintype "passive"))
      (node (ref "D7") (pin "K1") (pinfunction "IO_L2P_T0_34_K1") (pintype "bidirectional"))
    )
    (net (code "16") (name "/ADC_6_7_B_n") (class "Default")
      (node (ref "D15") (pin "29") (pinfunction "D2_6_7-_29") (pintype "passive"))
      (node (ref "D7") (pin "V2") (pinfunction "IO_L15N_T2_DQS_34_V2") (pintype "bidirectional"))
    )
    (net (code "17") (name "/ADC_6_7_B_p") (class "Default")
      (node (ref "D15") (pin "30") (pinfunction "D2_6_7+_30") (pintype "passive"))
      (node (ref "D7") (pin "U2") (pinfunction "IO_L15P_T2_DQS_34_U2") (pintype "bidirectional"))
    )
    (net (code "18") (name "/ADC_8_9_A_n") (class "Default")
      (node (ref "D15") (pin "51") (pinfunction "D1_8_9-_51") (pintype "passive"))
      (node (ref "D7") (pin "M3") (pinfunction "IO_L1N_T0_34_M3") (pintype "bidirectional"))
    )
    (net (code "19") (name "/ADC_8_9_A_p") (class "Default")
      (node (ref "D15") (pin "52") (pinfunction "D1_8_9+_52") (pintype "passive"))
      (node (ref "D7") (pin "L3") (pinfunction "IO_L1P_T0_34_L3") (pintype "bidirectional"))
    )
    (net (code "20") (name "/ADC_8_9_B_n") (class "Default")
      (node (ref "D15") (pin "31") (pinfunction "D2_8_9-_31") (pintype "passive"))
      (node (ref "D7") (pin "AB1") (pinfunction "IO_L22N_T3_34_AB1") (pintype "bidirectional"))
    )
    (net (code "21") (name "/ADC_8_9_B_p") (class "Default")
      (node (ref "D15") (pin "32") (pinfunction "D2_8_9+_32") (pintype "passive"))
      (node (ref "D7") (pin "AA1") (pinfunction "IO_L22P_T3_34_AA1") (pintype "bidirectional"))
    )
    (net (code "22") (name "/ADC_10_11_A_n") (class "Default")
      (node (ref "D15") (pin "53") (pinfunction "D1_10_11-_53") (pintype "passive"))
      (node (ref "D7") (pin "N4") (pinfunction "IO_L9N_T1_DQS_34_N4") (pintype "bidirectional"))
    )
    (net (code "23") (name "/ADC_10_11_A_p") (class "Default")
      (node (ref "D15") (pin "54") (pinfunction "D1_10_11+_54") (pintype "passive"))
      (node (ref "D7") (pin "M5") (pinfunction "IO_L9P_T1_DQS_34_M5") (pintype "bidirectional"))
    )
    (net (code "24") (name "/ADC_10_11_B_n") (class "Default")
      (node (ref "D15") (pin "33") (pinfunction "D2_10_11-_33") (pintype "passive"))
      (node (ref "D7") (pin "Y1") (pinfunction "IO_L20N_T3_34_Y1") (pintype "bidirectional"))
    )
    (net (code "25") (name "/ADC_10_11_B_p") (class "Default")
      (node (ref "D15") (pin "34") (pinfunction "D2_10_11+_34") (pintype "passive"))
      (node (ref "D7") (pin "W1") (pinfunction "IO_L20P_T3_34_W1") (pintype "bidirectional"))
    )
    (net (code "26") (name "/ADC_12_13_A_n") (class "Default")
      (node (ref "D15") (pin "55") (pinfunction "D1_12_13-_55") (pintype "passive"))
      (node (ref "D7") (pin "L4") (pinfunction "IO_L6N_T0_VREF_34_L4") (pintype "bidirectional"))
    )
    (net (code "27") (name "/ADC_12_13_A_p") (class "Default")
      (node (ref "D15") (pin "56") (pinfunction "D1_12_13+_56") (pintype "passive"))
      (node (ref "D7") (pin "L5") (pinfunction "IO_L6P_T0_34_L5") (pintype "bidirectional"))
    )
    (net (code "28") (name "/ADC_12_13_B_n") (class "Default")
      (node (ref "D15") (pin "35") (pinfunction "D2_12_13-_35") (pintype "passive"))
      (node (ref "D7") (pin "R4") (pinfunction "IO_L11N_T1_SRCC_34_R4") (pintype "bidirectional"))
    )
    (net (code "29") (name "/ADC_12_13_B_p") (class "Default")
      (node (ref "D15") (pin "36") (pinfunction "D2_12_13+_36") (pintype "passive"))
      (node (ref "D7") (pin "P4") (pinfunction "IO_L11P_T1_SRCC_34_P4") (pintype "bidirectional"))
    )
    (net (code "30") (name "/ADC_14_15_A_n") (class "Default")
      (node (ref "D15") (pin "57") (pinfunction "D1_14_15-_57") (pintype "passive"))
      (node (ref "D7") (pin "K2") (pinfunction "IO_L4N_T0_34_K2") (pintype "bidirectional"))
    )
    (net (code "31") (name "/ADC_14_15_A_p") (class "Default")
      (node (ref "D15") (pin "58") (pinfunction "D1_14_15+_58") (pintype "passive"))
      (node (ref "D7") (pin "K3") (pinfunction "IO_L4P_T0_34_K3") (pintype "bidirectional"))
    )
    (net (code "32") (name "/ADC_14_15_B_n") (class "Default")
      (node (ref "D15") (pin "37") (pinfunction "D2_14_15-_37") (pintype "passive"))
      (node (ref "D7") (pin "U1") (pinfunction "IO_L10N_T1_34_U1") (pintype "bidirectional"))
    )
    (net (code "33") (name "/ADC_14_15_B_p") (class "Default")
      (node (ref "D15") (pin "38") (pinfunction "D2_14_15+_38") (pintype "passive"))
      (node (ref "D7") (pin "T1") (pinfunction "IO_L10P_T1_34_T1") (pintype "bidirectional"))
    )
    (net (code "34") (name "/ADC_CLKOUT_n") (class "Default")
      (node (ref "D15") (pin "39") (pinfunction "CLKOUT-_39") (pintype "passive"))
      (node (ref "D7") (pin "T3") (pinfunction "IO_L12N_T1_MRCC_34_T3") (pintype "bidirectional"))
    )
    (net (code "35") (name "/ADC_CLKOUT_p") (class "Default")
      (node (ref "D15") (pin "40") (pinfunction "CLKOUT+_40") (pintype "passive"))
      (node (ref "D7") (pin "R3") (pinfunction "IO_L12P_T1_MRCC_34_R3") (pintype "bidirectional"))
    )
    (net (code "36") (name "/ADC_OF2_1_n") (class "Default")
      (node (ref "D15") (pin "59") (pinfunction "OF2_1-_59") (pintype "passive"))
      (node (ref "D7") (pin "N2") (pinfunction "IO_L5N_T0_34_N2") (pintype "bidirectional"))
    )
    (net (code "37") (name "/ADC_OF2_1_p") (class "Default")
      (node (ref "D15") (pin "60") (pinfunction "OF2_1+_60") (pintype "passive"))
      (node (ref "D7") (pin "N3") (pinfunction "IO_L5P_T0_34_N3") (pintype "bidirectional"))
    )
    (net (code "38") (name "/ADC_SCLK") (class "Default")
      (node (ref "D15") (pin "21") (pinfunction "SCK_21") (pintype "passive"))
      (node (ref "D7") (pin "AB3") (pinfunction "IO_L24N_T3_34_AB3") (pintype "bidirectional"))
    )
    (net (code "39") (name "/ADC_SDI") (class "Default")
      (node (ref "D15") (pin "22") (pinfunction "SDI_22") (pintype "passive"))
      (node (ref "D7") (pin "AA4") (pinfunction "IO_L24P_T3_34_AA4") (pintype "bidirectional"))
    )
    (net (code "40") (name "/ADC_SDO") (class "Default")
      (node (ref "D15") (pin "61") (pinfunction "SDO_61") (pintype "passive"))
      (node (ref "D7") (pin "K4") (pinfunction "IO_0_VRN_34_K4") (pintype "bidirectional"))
      (node (ref "R97") (pin "2") (pinfunction "2_2") (pintype "passive"))
    )
    (net (code "41") (name "/ADC_SEN") (class "Default")
      (node (ref "D15") (pin "20") (pinfunction "~{CS}_20") (pintype "passive"))
      (node (ref "D7") (pin "AB2") (pinfunction "IO_L23N_T3_34_AB2") (pintype "bidirectional"))
    )
    (net (code "42") (name "/AIN1_N") (class "Default")
      (node (ref "D15") (pin "5") (pinfunction "Ain1-_5") (pintype "passive"))
      (node (ref "L18") (pin "2") (pinfunction "2_2") (pintype "passive"))
      (node (ref "R64") (pin "2") (pinfunction "2_2") (pintype "passive"))
      (node (ref "R66") (pin "1") (pinfunction "1_1") (pintype "passive"))
    )
    (net (code "43") (name "/AIN1_P") (class "Default")
      (node (ref "D15") (pin "4") (pinfunction "Ain1+_4") (pintype "passive"))
      (node (ref "L20") (pin "2") (pinfunction "2_2") (pintype "passive"))
      (node (ref "R67") (pin "2") (pinfunction "2_2") (pintype "passive"))
      (node (ref "R76") (pin "2") (pinfunction "2_2") (pintype "passive"))
    )
    (net (code "44") (name "/AIN2_N") (class "Default")
      (node (ref "D15") (pin "13") (pinfunction "Ain2-_13") (pintype "passive"))
      (node (ref "L22") (pin "2") (pinfunction "2_2") (pintype "passive"))
      (node (ref "R79") (pin "2") (pinfunction "2_2") (pintype "passive"))
      (node (ref "R82") (pin "2") (pinfunction "2_2") (pintype "passive"))
    )
    (net (code "45") (name "/AIN2_P") (class "Default")
      (node (ref "D15") (pin "12") (pinfunction "Ain2+_12") (pintype "passive"))
      (node (ref "L24") (pin "2") (pinfunction "2_2") (pintype "passive"))
      (node (ref "R83") (pin "2") (pinfunction "2_2") (pintype "passive"))
      (node (ref "R91") (pin "2") (pinfunction "2_2") (pintype "passive"))
    )
    (net (code "46") (name "/CLK_ADC_N") (class "Default")
      (node (ref "D15") (pin "19") (pinfunction "ENC-_19") (pintype "passive"))
      (node (ref "R96") (pin "1") (pinfunction "1_1") (pintype "passive"))
    )
    (net (code "47") (name "/CLK_ADC_P") (class "Default")
      (node (ref "D15") (pin "18") (pinfunction "ENC+_18") (pintype "passive"))
      (node (ref "R96") (pin "2") (pinfunction "2_2") (pintype "passive"))
    )
    (net (code "48") (name "/CLK_DAC_N") (class "Default")
      (node (ref "D18") (pin "61") (pinfunction "DACCLKN_61") (pintype "passive"))
      (node (ref "R94") (pin "1") (pinfunction "1_1") (pintype "passive"))
    )
    (net (code "49") (name "/CLK_DAC_P") (class "Default")
      (node (ref "D18") (pin "62") (pinfunction "DACCLKP_62") (pintype "passive"))
      (node (ref "R94") (pin "2") (pinfunction "2_2") (pintype "passive"))
    )
    (net (code "50") (name "/CLK_DAC_REF_N") (class "Default")
      (node (ref "D18") (pin "3") (pinfunction "REFPN/SYNCN_3") (pintype "passive"))
      (node (ref "R95") (pin "1") (pinfunction "1_1") (pintype "passive"))
    )
    (net (code "51") (name "/CLK_DAC_REF_P") (class "Default")
      (node (ref "D18") (pin "2") (pinfunction "REFP/SYNCP_2") (pintype "passive"))
      (node (ref "R95") (pin "2") (pinfunction "2_2") (pintype "passive"))
    )
    (net (code "52") (name "/CLK_FPGA_N") (class "Default")
      (node (ref "D7") (pin "Y9") (pinfunction "IO_L13N_T2_MRCC_33_Y9") (pintype "bidirectional"))
    )
    (net (code "53") (name "/CLK_FPGA_P") (class "Default")
      (node (ref "D7") (pin "W9") (pinfunction "IO_L13P_T2_MRCC_33_W9") (pintype "bidirectional"))
    )
    (net (code "54") (name "/DAC_CS") (class "Default")
      (node (ref "D18") (pin "54") (pinfunction "~{CS}_54") (pintype "passive"))
      (node (ref "D7") (pin "V13") (pinfunction "IO_L23P_T3_33_V13") (pintype "bidirectional"))
    )
    (net (code "55") (name "/DAC_D0_N") (class "Default")
      (node (ref "D18") (pin "47") (pinfunction "D0N_47") (pintype "passive"))
      (node (ref "D7") (pin "V8") (pinfunction "IO_L9N_T1_DQS_33_V8") (pintype "bidirectional"))
    )
    (net (code "56") (name "/DAC_D0_P") (class "Default")
      (node (ref "D18") (pin "46") (pinfunction "D0P_46") (pintype "passive"))
      (node (ref "D7") (pin "U8") (pinfunction "IO_L9P_T1_DQS_33_U8") (pintype "bidirectional"))
    )
    (net (code "57") (name "/DAC_D1_N") (class "Default")
      (node (ref "D18") (pin "45") (pinfunction "D1N_45") (pintype "passive"))
      (node (ref "D7") (pin "T8") (pinfunction "IO_L18N_T2_33_T8") (pintype "bidirectional"))
    )
    (net (code "58") (name "/DAC_D1_P") (class "Default")
      (node (ref "D18") (pin "44") (pinfunction "D1P_44") (pintype "passive"))
      (node (ref "D7") (pin "T9") (pinfunction "IO_L18P_T2_33_T9") (pintype "bidirectional"))
    )
    (net (code "59") (name "/DAC_D2_N") (class "Default")
      (node (ref "D18") (pin "42") (pinfunction "D2N_42") (pintype "passive"))
      (node (ref "D7") (pin "R6") (pinfunction "IO_L8N_T1_33_R6") (pintype "bidirectional"))
    )
    (net (code "60") (name "/DAC_D2_P") (class "Default")
      (node (ref "D18") (pin "41") (pinfunction "D2P_41") (pintype "passive"))
      (node (ref "D7") (pin "R7") (pinfunction "IO_L8P_T1_33_R7") (pintype "bidirectional"))
    )
    (net (code "61") (name "/DAC_D3_N") (class "Default")
      (node (ref "D18") (pin "40") (pinfunction "D3N_40") (pintype "passive"))
      (node (ref "D7") (pin "U6") (pinfunction "IO_L10N_T1_33_U6") (pintype "bidirectional"))
    )
    (net (code "62") (name "/DAC_D3_P") (class "Default")
      (node (ref "D18") (pin "39") (pinfunction "D3P_39") (pintype "passive"))
      (node (ref "D7") (pin "U7") (pinfunction "IO_L10P_T1_33_U7") (pintype "bidirectional"))
    )
    (net (code "63") (name "/DAC_D4_N") (class "Default")
      (node (ref "D18") (pin "38") (pinfunction "D4N_38") (pintype "passive"))
      (node (ref "D7") (pin "AB5") (pinfunction "IO_L1N_T0_33_AB5") (pintype "bidirectional"))
    )
    (net (code "64") (name "/DAC_D4_P") (class "Default")
      (node (ref "D18") (pin "37") (pinfunction "D4P_37") (pintype "passive"))
      (node (ref "D7") (pin "AA5") (pinfunction "IO_L1P_T0_33_AA5") (pintype "bidirectional"))
    )
    (net (code "65") (name "/DAC_D5_N") (class "Default")
      (node (ref "D18") (pin "35") (pinfunction "D5N_35") (pintype "passive"))
      (node (ref "D7") (pin "AB6") (pinfunction "IO_L3N_T0_DQS_33_AB6") (pintype "bidirectional"))
    )
    (net (code "66") (name "/DAC_D5_P") (class "Default")
      (node (ref "D18") (pin "34") (pinfunction "D5P_34") (pintype "passive"))
      (node (ref "D7") (pin "AA6") (pinfunction "IO_L3P_T0_DQS_33_AA6") (pintype "bidirectional"))
    )
    (net (code "67") (name "/DAC_D6_N") (class "Default")
      (node (ref "D18") (pin "33") (pinfunction "D6N_33") (pintype "passive"))
      (node (ref "D7") (pin "Y6") (pinfunction "IO_L7N_T1_33_Y6") (pintype "bidirectional"))
    )
    (net (code "68") (name "/DAC_D6_P") (class "Default")
      (node (ref "D18") (pin "32") (pinfunction "D6P_32") (pintype "passive"))
      (node (ref "D7") (pin "W6") (pinfunction "IO_L7P_T1_33_W6") (pintype "bidirectional"))
    )
    (net (code "69") (name "/DAC_D7_N") (class "Default")
      (node (ref "D18") (pin "31") (pinfunction "D7N_31") (pintype "passive"))
      (node (ref "D7") (pin "AB7") (pinfunction "IO_L2N_T0_33_AB7") (pintype "bidirectional"))
    )
    (net (code "70") (name "/DAC_D7_P") (class "Default")
      (node (ref "D18") (pin "30") (pinfunction "D7P_30") (pintype "passive"))
      (node (ref "D7") (pin "AB8") (pinfunction "IO_L2P_T0_33_AB8") (pintype "bidirectional"))
    )
    (net (code "71") (name "/DAC_D8_N") (class "Default")
      (node (ref "D18") (pin "27") (pinfunction "D8N_27") (pintype "passive"))
      (node (ref "D7") (pin "AB10") (pinfunction "IO_L4N_T0_33_AB10") (pintype "bidirectional"))
    )
    (net (code "72") (name "/DAC_D8_P") (class "Default")
      (node (ref "D18") (pin "26") (pinfunction "D8P_26") (pintype "passive"))
      (node (ref "D7") (pin "AA10") (pinfunction "IO_L4P_T0_33_AA10") (pintype "bidirectional"))
    )
    (net (code "73") (name "/DAC_D9_N") (class "Default")
      (node (ref "D18") (pin "25") (pinfunction "D9N_25") (pintype "passive"))
      (node (ref "D7") (pin "AA8") (pinfunction "IO_L5N_T0_33_AA8") (pintype "bidirectional"))
    )
    (net (code "74") (name "/DAC_D9_P") (class "Default")
      (node (ref "D18") (pin "24") (pinfunction "D9P_24") (pintype "passive"))
      (node (ref "D7") (pin "AA9") (pinfunction "IO_L5P_T0_33_AA9") (pintype "bidirectional"))
    )
    (net (code "75") (name "/DAC_D10_N") (class "Default")
      (node (ref "D18") (pin "23") (pinfunction "D10N_23") (pintype "passive"))
      (node (ref "D7") (pin "AB11") (pinfunction "IO_L20N_T3_33_AB11") (pintype "bidirectional"))
    )
    (net (code "76") (name "/DAC_D10_P") (class "Default")
      (node (ref "D18") (pin "22") (pinfunction "D10P_22") (pintype "passive"))
      (node (ref "D7") (pin "AA11") (pinfunction "IO_L20P_T3_33_AA11") (pintype "bidirectional"))
    )
    (net (code "77") (name "/DAC_D11_N") (class "Default")
      (node (ref "D18") (pin "21") (pinfunction "D11N_21") (pintype "passive"))
      (node (ref "D7") (pin "Y11") (pinfunction "IO_L6N_T0_VREF_33_Y11") (pintype "bidirectional"))
    )
    (net (code "78") (name "/DAC_D11_P") (class "Default")
      (node (ref "D18") (pin "20") (pinfunction "D11P_20") (pintype "passive"))
      (node (ref "D7") (pin "W11") (pinfunction "IO_L6P_T0_33_W11") (pintype "bidirectional"))
    )
    (net (code "79") (name "/DAC_D12_N") (class "Default")
      (node (ref "D18") (pin "18") (pinfunction "D12N_18") (pintype "passive"))
      (node (ref "D7") (pin "U11") (pinfunction "IO_L17N_T2_33_U11") (pintype "bidirectional"))
    )
    (net (code "80") (name "/DAC_D12_P") (class "Default")
      (node (ref "D18") (pin "17") (pinfunction "D12P_17") (pintype "passive"))
      (node (ref "D7") (pin "U12") (pinfunction "IO_L17P_T2_33_U12") (pintype "bidirectional"))
    )
    (net (code "81") (name "/DAC_D13_N") (class "Default")
      (node (ref "D18") (pin "16") (pinfunction "D13N_16") (pintype "passive"))
      (node (ref "D7") (pin "T10") (pinfunction "IO_L16N_T2_33_T10") (pintype "bidirectional"))
    )
    (net (code "82") (name "/DAC_D13_P") (class "Default")
      (node (ref "D18") (pin "15") (pinfunction "D13P_15") (pintype "passive"))
      (node (ref "D7") (pin "T11") (pinfunction "IO_L16P_T2_33_T11") (pintype "bidirectional"))
    )
    (net (code "83") (name "/DAC_D14_N") (class "Default")
      (node (ref "D18") (pin "14") (pinfunction "D14N_14") (pintype "passive"))
      (node (ref "D7") (pin "W10") (pinfunction "IO_L15N_T2_DQS_33_W10") (pintype "bidirectional"))
    )
    (net (code "84") (name "/DAC_D14_P") (class "Default")
      (node (ref "D18") (pin "13") (pinfunction "D14P_13") (pintype "passive"))
      (node (ref "D7") (pin "V10") (pinfunction "IO_L15P_T2_DQS_33_V10") (pintype "bidirectional"))
    )
    (net (code "85") (name "/DAC_D15_N") (class "Default")
      (node (ref "D18") (pin "11") (pinfunction "D15N_11") (pintype "passive"))
      (node (ref "D7") (pin "Y12") (pinfunction "IO_L19N_T3_VREF_33_Y12") (pintype "bidirectional"))
    )
    (net (code "86") (name "/DAC_D15_P") (class "Default")
      (node (ref "D18") (pin "10") (pinfunction "D15P_10") (pintype "passive"))
      (node (ref "D7") (pin "W12") (pinfunction "IO_L19P_T3_33_W12") (pintype "bidirectional"))
    )
    (net (code "87") (name "/DAC_DCI_N") (class "Default")
      (node (ref "D18") (pin "29") (pinfunction "DCIN_29") (pintype "passive"))
      (node (ref "D7") (pin "W7") (pinfunction "IO_L11N_T1_SRCC_33_W7") (pintype "bidirectional"))
    )
    (net (code "88") (name "/DAC_DCI_P") (class "Default")
      (node (ref "D18") (pin "28") (pinfunction "DCIP_28") (pintype "passive"))
      (node (ref "D7") (pin "V7") (pinfunction "IO_L11P_T1_SRCC_33_V7") (pintype "bidirectional"))
    )
    (net (code "89") (name "/DAC_FRAME_N") (class "Default")
      (node (ref "D18") (pin "9") (pinfunction "FRAMEN/PARITYN_9") (pintype "passive"))
      (node (ref "D7") (pin "V9") (pinfunction "IO_L14N_T2_SRCC_33_V9") (pintype "bidirectional"))
    )
    (net (code "90") (name "/DAC_FRAME_P") (class "Default")
      (node (ref "D18") (pin "8") (pinfunction "FRAMEP/PARITYP_8") (pintype "passive"))
      (node (ref "D7") (pin "U10") (pinfunction "IO_L14P_T2_SRCC_33_U10") (pintype "bidirectional"))
    )
    (net (code "91") (name "/DAC_IRQ1") (class "Default")
      (node (ref "D18") (pin "51") (pinfunction "~{IRQ1}_51") (pintype "passive"))
      (node (ref "D7") (pin "V5") (pinfunction "IO_25_VRP_34_V5") (pintype "bidirectional"))
    )
    (net (code "92") (name "/DAC_IRQ2") (class "Default")
      (node (ref "D18") (pin "50") (pinfunction "~{IRQ2}_50") (pintype "passive"))
      (node (ref "D7") (pin "T6") (pinfunction "IO_0_VRN_33_T6") (pintype "bidirectional"))
    )
    (net (code "93") (name "/DAC_RESET") (class "Default")
      (node (ref "D18") (pin "5") (pinfunction "~{RESET}_5") (pintype "passive"))
      (node (ref "D7") (pin "V12") (pinfunction "IO_L23N_T3_33_V12") (pintype "bidirectional"))
    )
    (net (code "94") (name "/DAC_SCLK") (class "Default")
      (node (ref "D18") (pin "53") (pinfunction "SCLK_53") (pintype "passive"))
      (node (ref "D7") (pin "U13") (pinfunction "IO_L24N_T3_33_U13") (pintype "bidirectional"))
    )
    (net (code "95") (name "/DAC_SDIO") (class "Default")
      (node (ref "D18") (pin "52") (pinfunction "SDIO_52") (pintype "passive"))
      (node (ref "D7") (pin "AB13") (pinfunction "IO_L22P_T3_33_AB13") (pintype "bidirectional"))
    )
    (net (code "96") (name "/DAC_TXEN") (class "Default")
      (node (ref "D18") (pin "6") (pinfunction "TXEN_6") (pintype "passive"))
      (node (ref "D7") (pin "AB12") (pinfunction "IO_L22N_T3_33_AB12") (pintype "bidirectional"))
    )
    (net (code "97") (name "/DVDD_DAC") (class "Default")
      (node (ref "C223") (pin "1") (pinfunction "1_1") (pintype "passive"))
      (node (ref "C225") (pin "1") (pinfunction "1_1") (pintype "passive"))
      (node (ref "C227") (pin "1") (pinfunction "1_1") (pintype "passive"))
      (node (ref "C229") (pin "1") (pinfunction "1_1") (pintype "passive"))
      (node (ref "C231") (pin "1") (pinfunction "1_1") (pintype "passive"))
      (node (ref "C233") (pin "1") (pinfunction "1_1") (pintype "passive"))
      (node (ref "C235") (pin "1") (pinfunction "1_1") (pintype "passive"))
      (node (ref "D18") (pin "12") (pinfunction "DVDD18_12") (pintype "passive"))
      (node (ref "D18") (pin "19") (pinfunction "DVDD18_19") (pintype "passive"))
      (node (ref "D18") (pin "36") (pinfunction "DVDD18_36") (pintype "passive"))
      (node (ref "D18") (pin "43") (pinfunction "DVDD18_43") (pintype "passive"))
      (node (ref "D18") (pin "48") (pinfunction "DVDD18_48") (pintype "passive"))
      (node (ref "D18") (pin "49") (pinfunction "DVDD18_49") (pintype "passive"))
      (node (ref "D18") (pin "7") (pinfunction "DVDD18_7") (pintype "passive"))
    )
    (net (code "98") (name "/IOUTA_N") (class "Default")
      (node (ref "D18") (pin "56") (pinfunction "IOUT2P_56") (pintype "passive"))
    )
    (net (code "99") (name "/IOUTA_P") (class "Default")
      (node (ref "D18") (pin "57") (pinfunction "IOUT2N_57") (pintype "passive"))
    )
    (net (code "100") (name "/IOUTB_N") (class "Default")
      (node (ref "D18") (pin "67") (pinfunction "IOUT1P_67") (pintype "passive"))
    )
    (net (code "101") (name "/IOUTB_P") (class "Default")
      (node (ref "D18") (pin "66") (pinfunction "IOUT1N_66") (pintype "passive"))
    )
    (net (code "102") (name "/VINA_N") (class "Default")
      (node (ref "R86") (pin "2") (pinfunction "2_2") (pintype "passive"))
    )
    (net (code "103") (name "/VINA_P") (class "Default")
      (node (ref "R85") (pin "2") (pinfunction "2_2") (pintype "passive"))
    )
    (net (code "104") (name "/VINB_N") (class "Default")
      (node (ref "R71") (pin "2") (pinfunction "2_2") (pintype "passive"))
    )
    (net (code "105") (name "/VINB_P") (class "Default")
      (node (ref "R70") (pin "2") (pinfunction "2_2") (pintype "passive"))
    )
    (net (code "106") (name "1V8_adc_avdd") (class "Default")
      (node (ref "C205") (pin "2") (pinfunction "2_2") (pintype "passive"))
      (node (ref "C206") (pin "2") (pinfunction "2_2") (pintype "passive"))
      (node (ref "C242") (pin "2") (pinfunction "2_2") (pintype "passive"))
      (node (ref "D20") (pin "3") (pinfunction "OUT_3") (pintype "passive"))
      (node (ref "L26") (pin "1") (pinfunction "1_1") (pintype "passive"))
    )
    (net (code "107") (name "1V8_cvdd_dac") (class "Default")
      (node (ref "C212") (pin "2") (pinfunction "2_2") (pintype "passive"))
      (node (ref "C213") (pin "2") (pinfunction "2_2") (pintype "passive"))
      (node (ref "C252") (pin "2") (pinfunction "2_2") (pintype "passive"))
      (node (ref "D21") (pin "3") (pinfunction "OUT_3") (pintype "passive"))
      (node (ref "L29") (pin "1") (pinfunction "1_1") (pintype "passive"))
    )
    (net (code "108") (name "3V3_dac_avdd") (class "Default")
      (node (ref "C217") (pin "2") (pinfunction "2_2") (pintype "passive"))
      (node (ref "C218") (pin "2") (pinfunction "2_2") (pintype "passive"))
      (node (ref "C253") (pin "2") (pinfunction "2_2") (pintype "passive"))
      (node (ref "D22") (pin "3") (pinfunction "OUT_3") (pintype "passive"))
      (node (ref "L30") (pin "1") (pinfunction "1_1") (pintype "passive"))
    )
    (net (code "109") (name "5V0_op_avdd") (class "Default")
      (node (ref "C200") (pin "2") (pinfunction "2_2") (pintype "passive"))
      (node (ref "C201") (pin "2") (pinfunction "2_2") (pintype "passive"))
      (node (ref "C241") (pin "2") (pinfunction "2_2") (pintype "passive"))
      (node (ref "D19") (pin "3") (pinfunction "OUT_3") (pintype "passive"))
      (node (ref "L25") (pin "1") (pinfunction "1_1") (pintype "passive"))
    )
    (net (code "110") (name "5V_AVDD") (class "Default")
      (node (ref "C202") (pin "2") (pinfunction "2_2") (pintype "passive"))
      (node (ref "C203") (pin "2") (pinfunction "2_2") (pintype "passive"))
      (node (ref "C204") (pin "2") (pinfunction "2_2") (pintype "passive"))
      (node (ref "D16") (pin "4") (pinfunction "Vs+_4") (pintype "passive"))
      (node (ref "D16") (pin "9") (pinfunction "Vs+_9") (pintype "passive"))
      (node (ref "D17") (pin "4") (pinfunction "Vs+_4") (pintype "passive"))
      (node (ref "D17") (pin "9") (pinfunction "Vs+_9") (pintype "passive"))
      (node (ref "L25") (pin "2") (pinfunction "2_2") (pintype "passive"))
    )
    (net (code "111") (name "AGND_ADC") (class "Default")
      (node (ref "C183") (pin "1") (pinfunction "1_1") (pintype "passive"))
      (node (ref "C185") (pin "2") (pinfunction "2_2") (pintype "passive"))
      (node (ref "C186") (pin "1") (pinfunction "1_1") (pintype "passive"))
      (node (ref "C188") (pin "1") (pinfunction "1_1") (pintype "passive"))
      (node (ref "C190") (pin "2") (pinfunction "2_2") (pintype "passive"))
      (node (ref "C191") (pin "1") (pinfunction "1_1") (pintype "passive"))
      (node (ref "C192") (pin "2") (pinfunction "2_2") (pintype "passive"))
      (node (ref "C193") (pin "1") (pinfunction "1_1") (pintype "passive"))
      (node (ref "C195") (pin "1") (pinfunction "1_1") (pintype "passive"))
      (node (ref "C196") (pin "2") (pinfunction "2_2") (pintype "passive"))
      (node (ref "C197") (pin "1") (pinfunction "1_1") (pintype "passive"))
      (node (ref "C198") (pin "2") (pinfunction "2_2") (pintype "passive"))
      (node (ref "C199") (pin "2") (pinfunction "2_2") (pintype "passive"))
      (node (ref "C202") (pin "1") (pinfunction "1_1") (pintype "passive"))
      (node (ref "C203") (pin "1") (pinfunction "1_1") (pintype "passive"))
      (node (ref "C204") (pin "1") (pinfunction "1_1") (pintype "passive"))
      (node (ref "C207") (pin "1") (pinfunction "1_1") (pintype "passive"))
      (node (ref "C208") (pin "1") (pinfunction "1_1") (pintype "passive"))
      (node (ref "C209") (pin "1") (pinfunction "1_1") (pintype "passive"))
      (node (ref "C210") (pin "2") (pinfunction "2_2") (pintype "passive"))
      (node (ref "C211") (pin "2") (pinfunction "2_2") (pintype "passive"))
      (node (ref "D15") (pin "14") (pinfunction "GND_14") (pintype "power_in"))
      (node (ref "D15") (pin "3") (pinfunction "GND_3") (pintype "power_in"))
      (node (ref "D15") (pin "6") (pinfunction "GND_6") (pintype "power_in"))
      (node (ref "D16") (pin "11") (pinfunction "Vs-_11") (pintype "passive"))
      (node (ref "D16") (pin "8") (pinfunction "Vs-_8") (pintype "passive"))
      (node (ref "D17") (pin "11") (pinfunction "Vs-_11") (pintype "passive"))
      (node (ref "D17") (pin "8") (pinfunction "Vs-_8") (pintype "passive"))
      (node (ref "L27") (pin "2") (pinfunction "2_2") (pintype "passive"))
      (node (ref "L28") (pin "2") (pinfunction "2_2") (pintype "passive"))
      (node (ref "R93") (pin "2") (pinfunction "2_2") (pintype "passive"))
    )
    (net (code "112") (name "AVDD_ADC") (class "Default")
      (node (ref "C198") (pin "1") (pinfunction "1_1") (pintype "passive"))
      (node (ref "C199") (pin "1") (pinfunction "1_1") (pintype "passive"))
      (node (ref "C207") (pin "2") (pinfunction "2_2") (pintype "passive"))
      (node (ref "C208") (pin "2") (pinfunction "2_2") (pintype "passive"))
      (node (ref "C209") (pin "2") (pinfunction "2_2") (pintype "passive"))
      (node (ref "C210") (pin "1") (pinfunction "1_1") (pintype "passive"))
      (node (ref "C211") (pin "1") (pinfunction "1_1") (pintype "passive"))
      (node (ref "D15") (pin "1") (pinfunction "VDD_1") (pintype "power_in"))
      (node (ref "D15") (pin "16") (pinfunction "VDD_16") (pintype "power_in"))
      (node (ref "D15") (pin "17") (pinfunction "VDD_17") (pintype "power_in"))
      (node (ref "D15") (pin "64") (pinfunction "VDD_64") (pintype "power_in"))
      (node (ref "L26") (pin "2") (pinfunction "2_2") (pintype "passive"))
      (node (ref "R92") (pin "2") (pinfunction "2_2") (pintype "passive"))
    )
    (net (code "113") (name "AVDD_DAC") (class "Default")
      (node (ref "C219") (pin "2") (pinfunction "2_2") (pintype "passive"))
      (node (ref "C220") (pin "2") (pinfunction "2_2") (pintype "passive"))
      (node (ref "C221") (pin "2") (pinfunction "2_2") (pintype "passive"))
      (node (ref "C243") (pin "2") (pinfunction "2_2") (pintype "passive"))
      (node (ref "C244") (pin "2") (pinfunction "2_2") (pintype "passive"))
      (node (ref "C245") (pin "2") (pinfunction "2_2") (pintype "passive"))
      (node (ref "C247") (pin "2") (pinfunction "2_2") (pintype "passive"))
      (node (ref "D18") (pin "55") (pinfunction "AVDD33_55") (pintype "passive"))
      (node (ref "D18") (pin "58") (pinfunction "AVDD33_58") (pintype "passive"))
      (node (ref "D18") (pin "65") (pinfunction "AVDD33_65") (pintype "passive"))
      (node (ref "D18") (pin "68") (pinfunction "AVDD33_68") (pintype "passive"))
      (node (ref "L30") (pin "2") (pinfunction "2_2") (pintype "passive"))
    )
    (net (code "114") (name "CVDD_DAC") (class "Default")
      (node (ref "C214") (pin "2") (pinfunction "2_2") (pintype "passive"))
      (node (ref "C215") (pin "2") (pinfunction "2_2") (pintype "passive"))
      (node (ref "C216") (pin "2") (pinfunction "2_2") (pintype "passive"))
      (node (ref "C222") (pin "2") (pinfunction "2_2") (pintype "passive"))
      (node (ref "C224") (pin "2") (pinfunction "2_2") (pintype "passive"))
      (node (ref "C226") (pin "2") (pinfunction "2_2") (pintype "passive"))
      (node (ref "C228") (pin "2") (pinfunction "2_2") (pintype "passive"))
      (node (ref "C230") (pin "2") (pinfunction "2_2") (pintype "passive"))
      (node (ref "C232") (pin "2") (pinfunction "2_2") (pintype "passive"))
      (node (ref "C234") (pin "2") (pinfunction "2_2") (pintype "passive"))
      (node (ref "C236") (pin "2") (pinfunction "2_2") (pintype "passive"))
      (node (ref "D18") (pin "1") (pinfunction "CVDD18_1") (pintype "passive"))
      (node (ref "D18") (pin "4") (pinfunction "CVDD18_4") (pintype "passive"))
      (node (ref "D18") (pin "59") (pinfunction "CVDD18_59") (pintype "passive"))
      (node (ref "D18") (pin "60") (pinfunction "CVDD18_60") (pintype "passive"))
      (node (ref "D18") (pin "63") (pinfunction "CVDD18_63") (pintype "passive"))
      (node (ref "D18") (pin "64") (pinfunction "CVDD18_64") (pintype "passive"))
      (node (ref "D18") (pin "71") (pinfunction "CVDD18_71") (pintype "passive"))
      (node (ref "D18") (pin "72") (pinfunction "CVDD18_72") (pintype "passive"))
      (node (ref "L29") (pin "2") (pinfunction "2_2") (pintype "passive"))
    )
    (net (code "115") (name "DVDD_ADC") (class "Default")
      (node (ref "C331") (pin "1") (pinfunction "1_1") (pintype "passive"))
      (node (ref "D15") (pin "42") (pinfunction "OVDD_42") (pintype "power_in"))
      (node (ref "R97") (pin "1") (pinfunction "1_1") (pintype "passive"))
    )
    (net (code "116") (name "GND") (class "Default")
      (node (ref "C200") (pin "1") (pinfunction "1_1") (pintype "passive"))
      (node (ref "C201") (pin "1") (pinfunction "1_1") (pintype "passive"))
      (node (ref "C205") (pin "1") (pinfunction "1_1") (pintype "passive"))
      (node (ref "C206") (pin "1") (pinfunction "1_1") (pintype "passive"))
      (node (ref "C212") (pin "1") (pinfunction "1_1") (pintype "passive"))
      (node (ref "C213") (pin "1") (pinfunction "1_1") (pintype "passive"))
      (node (ref "C214") (pin "1") (pinfunction "1_1") (pintype "passive"))
      (node (ref "C215") (pin "1") (pinfunction "1_1") (pintype "passive"))
      (node (ref "C216") (pin "1") (pinfunction "1_1") (pintype "passive"))
      (node (ref "C217") (pin "1") (pinfunction "1_1") (pintype "passive"))
      (node (ref "C218") (pin "1") (pinfunction "1_1") (pintype "passive"))
      (node (ref "C219") (pin "1") (pinfunction "1_1") (pintype "passive"))
      (node (ref "C220") (pin "1") (pinfunction "1_1") (pintype "passive"))
      (node (ref "C221") (pin "1") (pinfunction "1_1") (pintype "passive"))
      (node (ref "C222") (pin "1") (pinfunction "1_1") (pintype "passive"))
      (node (ref "C223") (pin "2") (pinfunction "2_2") (pintype "passive"))
      (node (ref "C224") (pin "1") (pinfunction "1_1") (pintype "passive"))
      (node (ref "C225") (pin "2") (pinfunction "2_2") (pintype "passive"))
      (node (ref "C226") (pin "1") (pinfunction "1_1") (pintype "passive"))
      (node (ref "C227") (pin "2") (pinfunction "2_2") (pintype "passive"))
      (node (ref "C228") (pin "1") (pinfunction "1_1") (pintype "passive"))
      (node (ref "C229") (pin "2") (pinfunction "2_2") (pintype "passive"))
      (node (ref "C230") (pin "1") (pinfunction "1_1") (pintype "passive"))
      (node (ref "C231") (pin "2") (pinfunction "2_2") (pintype "passive"))
      (node (ref "C232") (pin "1") (pinfunction "1_1") (pintype "passive"))
      (node (ref "C233") (pin "2") (pinfunction "2_2") (pintype "passive"))
      (node (ref "C234") (pin "1") (pinfunction "1_1") (pintype "passive"))
      (node (ref "C235") (pin "2") (pinfunction "2_2") (pintype "passive"))
      (node (ref "C236") (pin "1") (pinfunction "1_1") (pintype "passive"))
      (node (ref "C237") (pin "1") (pinfunction "1_1") (pintype "passive"))
      (node (ref "C238") (pin "1") (pinfunction "1_1") (pintype "passive"))
      (node (ref "C239") (pin "1") (pinfunction "1_1") (pintype "passive"))
      (node (ref "C240") (pin "1") (pinfunction "1_1") (pintype "passive"))
      (node (ref "C241") (pin "1") (pinfunction "1_1") (pintype "passive"))
      (node (ref "C242") (pin "1") (pinfunction "1_1") (pintype "passive"))
      (node (ref "C243") (pin "1") (pinfunction "1_1") (pintype "passive"))
      (node (ref "C244") (pin "1") (pinfunction "1_1") (pintype "passive"))
      (node (ref "C245") (pin "1") (pinfunction "1_1") (pintype "passive"))
      (node (ref "C246") (pin "1") (pinfunction "1_1") (pintype "passive"))
      (node (ref "C247") (pin "1") (pinfunction "1_1") (pintype "passive"))
      (node (ref "C248") (pin "1") (pinfunction "1_1") (pintype "passive"))
      (node (ref "C249") (pin "1") (pinfunction "1_1") (pintype "passive"))
      (node (ref "C250") (pin "1") (pinfunction "1_1") (pintype "passive"))
      (node (ref "C251") (pin "1") (pinfunction "1_1") (pintype "passive"))
      (node (ref "C252") (pin "1") (pinfunction "1_1") (pintype "passive"))
      (node (ref "C253") (pin "1") (pinfunction "1_1") (pintype "passive"))
      (node (ref "C331") (pin "2") (pinfunction "2_2") (pintype "passive"))
      (node (ref "D15") (pin "0") (pinfunction "EP_0") (pintype "power_in"))
      (node (ref "D15") (pin "11") (pinfunction "PAR/~{SER}_11") (pintype "passive"))
      (node (ref "D15") (pin "41") (pinfunction "OGND_41") (pintype "power_in"))
      (node (ref "D18") (pin "73") (pinfunction "EPAD_73") (pintype "passive"))
      (node (ref "D19") (pin "5") (pinfunction "GND_5") (pintype "passive"))
      (node (ref "D20") (pin "5") (pinfunction "GND_5") (pintype "passive"))
      (node (ref "D21") (pin "5") (pinfunction "GND_5") (pintype "passive"))
      (node (ref "D22") (pin "5") (pinfunction "GND_5") (pintype "passive"))
      (node (ref "L27") (pin "1") (pinfunction "1_1") (pintype "passive"))
      (node (ref "L28") (pin "1") (pinfunction "1_1") (pintype "passive"))
      (node (ref "R98") (pin "2") (pinfunction "2_2") (pintype "passive"))
    )
    (net (code "117") (name "Net-(C183-Pad2)") (class "Default")
      (node (ref "C183") (pin "2") (pinfunction "2_2") (pintype "passive"))
      (node (ref "L17") (pin "2") (pinfunction "2_2") (pintype "passive"))
      (node (ref "L18") (pin "1") (pinfunction "1_1") (pintype "passive"))
      (node (ref "R68") (pin "2") (pinfunction "2_2") (pintype "passive"))
    )
    (net (code "118") (name "Net-(C185-Pad1)") (class "Default")
      (node (ref "C185") (pin "1") (pinfunction "1_1") (pintype "passive"))
      (node (ref "L19") (pin "2") (pinfunction "2_2") (pintype "passive"))
      (node (ref "L20") (pin "1") (pinfunction "1_1") (pintype "passive"))
      (node (ref "R73") (pin "1") (pinfunction "1_1") (pintype "passive"))
    )
    (net (code "119") (name "Net-(C188-Pad2)") (class "Default")
      (node (ref "C188") (pin "2") (pinfunction "2_2") (pintype "passive"))
      (node (ref "L21") (pin "2") (pinfunction "2_2") (pintype "passive"))
      (node (ref "L22") (pin "1") (pinfunction "1_1") (pintype "passive"))
      (node (ref "R81") (pin "2") (pinfunction "2_2") (pintype "passive"))
    )
    (net (code "120") (name "Net-(C190-Pad1)") (class "Default")
      (node (ref "C190") (pin "1") (pinfunction "1_1") (pintype "passive"))
      (node (ref "L23") (pin "2") (pinfunction "2_2") (pintype "passive"))
      (node (ref "L24") (pin "1") (pinfunction "1_1") (pintype "passive"))
      (node (ref "R88") (pin "1") (pinfunction "1_1") (pintype "passive"))
    )
    (net (code "121") (name "Net-(C192-Pad1)") (class "Default")
      (node (ref "C192") (pin "1") (pinfunction "1_1") (pintype "passive"))
      (node (ref "C194") (pin "1") (pinfunction "1_1") (pintype "passive"))
      (node (ref "D15") (pin "7") (pinfunction "REFH_7") (pintype "passive"))
      (node (ref "D15") (pin "9") (pinfunction "REFH_9") (pintype "passive"))
    )
    (net (code "122") (name "Net-(C194-Pad2)") (class "Default")
      (node (ref "C194") (pin "2") (pinfunction "2_2") (pintype "passive"))
      (node (ref "C196") (pin "1") (pinfunction "1_1") (pintype "passive"))
      (node (ref "D15") (pin "10") (pinfunction "REFL_10") (pintype "passive"))
      (node (ref "D15") (pin "8") (pinfunction "REFL_8") (pintype "passive"))
    )
    (net (code "123") (name "Net-(D15A-SENSE)") (class "Default")
      (node (ref "D15") (pin "63") (pinfunction "SENSE_63") (pintype "passive"))
      (node (ref "R92") (pin "1") (pinfunction "1_1") (pintype "passive"))
      (node (ref "R93") (pin "1") (pinfunction "1_1") (pintype "passive"))
    )
    (net (code "124") (name "Net-(D15A-VREF)") (class "Default")
      (node (ref "C197") (pin "2") (pinfunction "2_2") (pintype "passive"))
      (node (ref "D15") (pin "62") (pinfunction "VREF_62") (pintype "passive"))
    )
    (net (code "125") (name "Net-(D16-IN+)") (class "Default")
      (node (ref "C184") (pin "1") (pinfunction "1_1") (pintype "passive"))
      (node (ref "D16") (pin "2") (pinfunction "IN+_2") (pintype "passive"))
      (node (ref "R65") (pin "1") (pinfunction "1_1") (pintype "passive"))
      (node (ref "R70") (pin "1") (pinfunction "1_1") (pintype "passive"))
    )
    (net (code "126") (name "Net-(D16-IN-)") (class "Default")
      (node (ref "C182") (pin "1") (pinfunction "1_1") (pintype "passive"))
      (node (ref "D16") (pin "6") (pinfunction "IN-_6") (pintype "passive"))
      (node (ref "R62") (pin "1") (pinfunction "1_1") (pintype "passive"))
      (node (ref "R71") (pin "1") (pinfunction "1_1") (pintype "passive"))
    )
    (net (code "127") (name "Net-(D16-OUT+)") (class "Default")
      (node (ref "C182") (pin "2") (pinfunction "2_2") (pintype "passive"))
      (node (ref "D16") (pin "7") (pinfunction "OUT+_7") (pintype "passive"))
      (node (ref "R62") (pin "2") (pinfunction "2_2") (pintype "passive"))
      (node (ref "R69") (pin "2") (pinfunction "2_2") (pintype "passive"))
    )
    (net (code "128") (name "Net-(D16-OUT-)") (class "Default")
      (node (ref "C184") (pin "2") (pinfunction "2_2") (pintype "passive"))
      (node (ref "D16") (pin "1") (pinfunction "OUT-_1") (pintype "passive"))
      (node (ref "R65") (pin "2") (pinfunction "2_2") (pintype "passive"))
      (node (ref "R72") (pin "2") (pinfunction "2_2") (pintype "passive"))
    )
    (net (code "129") (name "Net-(D16-Vocm)") (class "Default")
      (node (ref "C186") (pin "2") (pinfunction "2_2") (pintype "passive"))
      (node (ref "D16") (pin "5") (pinfunction "Vocm_5") (pintype "passive"))
      (node (ref "R74") (pin "1") (pinfunction "1_1") (pintype "passive"))
    )
    (net (code "130") (name "Net-(D17-IN+)") (class "Default")
      (node (ref "C189") (pin "1") (pinfunction "1_1") (pintype "passive"))
      (node (ref "D17") (pin "2") (pinfunction "IN+_2") (pintype "passive"))
      (node (ref "R80") (pin "1") (pinfunction "1_1") (pintype "passive"))
      (node (ref "R85") (pin "1") (pinfunction "1_1") (pintype "passive"))
    )
    (net (code "131") (name "Net-(D17-IN-)") (class "Default")
      (node (ref "C187") (pin "1") (pinfunction "1_1") (pintype "passive"))
      (node (ref "D17") (pin "6") (pinfunction "IN-_6") (pintype "passive"))
      (node (ref "R77") (pin "1") (pinfunction "1_1") (pintype "passive"))
      (node (ref "R86") (pin "1") (pinfunction "1_1") (pintype "passive"))
    )
    (net (code "132") (name "Net-(D17-OUT+)") (class "Default")
      (node (ref "C187") (pin "2") (pinfunction "2_2") (pintype "passive"))
      (node (ref "D17") (pin "7") (pinfunction "OUT+_7") (pintype "passive"))
      (node (ref "R77") (pin "2") (pinfunction "2_2") (pintype "passive"))
      (node (ref "R84") (pin "2") (pinfunction "2_2") (pintype "passive"))
    )
    (net (code "133") (name "Net-(D17-OUT-)") (class "Default")
      (node (ref "C189") (pin "2") (pinfunction "2_2") (pintype "passive"))
      (node (ref "D17") (pin "1") (pinfunction "OUT-_1") (pintype "passive"))
      (node (ref "R80") (pin "2") (pinfunction "2_2") (pintype "passive"))
      (node (ref "R87") (pin "2") (pinfunction "2_2") (pintype "passive"))
    )
    (net (code "134") (name "Net-(D17-Vocm)") (class "Default")
      (node (ref "C191") (pin "2") (pinfunction "2_2") (pintype "passive"))
      (node (ref "D17") (pin "5") (pinfunction "Vocm_5") (pintype "passive"))
      (node (ref "R89") (pin "1") (pinfunction "1_1") (pintype "passive"))
    )
    (net (code "135") (name "Net-(D18C-FSADJ)") (class "Default")
      (node (ref "D18") (pin "69") (pinfunction "FSADJ_69") (pintype "passive"))
      (node (ref "R98") (pin "1") (pinfunction "1_1") (pintype "passive"))
    )
    (net (code "136") (name "Net-(D18C-VREF)") (class "Default")
      (node (ref "C246") (pin "2") (pinfunction "2_2") (pintype "passive"))
      (node (ref "D18") (pin "70") (pinfunction "VREF_70") (pintype "passive"))
    )
    (net (code "137") (name "Net-(L17-Pad1)") (class "Default")
      (node (ref "L17") (pin "1") (pinfunction "1_1") (pintype "passive"))
      (node (ref "R63") (pin "1") (pinfunction "1_1") (pintype "passive"))
      (node (ref "R69") (pin "1") (pinfunction "1_1") (pintype "passive"))
    )
    (net (code "138") (name "Net-(L19-Pad1)") (class "Default")
      (node (ref "L19") (pin "1") (pinfunction "1_1") (pintype "passive"))
      (node (ref "R72") (pin "1") (pinfunction "1_1") (pintype "passive"))
      (node (ref "R75") (pin "1") (pinfunction "1_1") (pintype "passive"))
    )
    (net (code "139") (name "Net-(L21-Pad1)") (class "Default")
      (node (ref "L21") (pin "1") (pinfunction "1_1") (pintype "passive"))
      (node (ref "R78") (pin "1") (pinfunction "1_1") (pintype "passive"))
      (node (ref "R84") (pin "1") (pinfunction "1_1") (pintype "passive"))
    )
    (net (code "140") (name "Net-(L23-Pad1)") (class "Default")
      (node (ref "L23") (pin "1") (pinfunction "1_1") (pintype "passive"))
      (node (ref "R87") (pin "1") (pinfunction "1_1") (pintype "passive"))
      (node (ref "R90") (pin "1") (pinfunction "1_1") (pintype "passive"))
    )
    (net (code "141") (name "Net-(R63-Pad2)") (class "Default")
      (node (ref "R63") (pin "2") (pinfunction "2_2") (pintype "passive"))
      (node (ref "R64") (pin "1") (pinfunction "1_1") (pintype "passive"))
      (node (ref "R68") (pin "1") (pinfunction "1_1") (pintype "passive"))
    )
    (net (code "142") (name "Net-(R73-Pad2)") (class "Default")
      (node (ref "R73") (pin "2") (pinfunction "2_2") (pintype "passive"))
      (node (ref "R75") (pin "2") (pinfunction "2_2") (pintype "passive"))
      (node (ref "R76") (pin "1") (pinfunction "1_1") (pintype "passive"))
    )
    (net (code "143") (name "Net-(R78-Pad2)") (class "Default")
      (node (ref "R78") (pin "2") (pinfunction "2_2") (pintype "passive"))
      (node (ref "R79") (pin "1") (pinfunction "1_1") (pintype "passive"))
      (node (ref "R81") (pin "1") (pinfunction "1_1") (pintype "passive"))
    )
    (net (code "144") (name "Net-(R88-Pad2)") (class "Default")
      (node (ref "R88") (pin "2") (pinfunction "2_2") (pintype "passive"))
      (node (ref "R90") (pin "2") (pinfunction "2_2") (pintype "passive"))
      (node (ref "R91") (pin "1") (pinfunction "1_1") (pintype "passive"))
    )
    (net (code "145") (name "VCM1") (class "Default")
      (node (ref "C193") (pin "2") (pinfunction "2_2") (pintype "passive"))
      (node (ref "D15") (pin "2") (pinfunction "VCM1_2") (pintype "passive"))
      (node (ref "R66") (pin "2") (pinfunction "2_2") (pintype "passive"))
      (node (ref "R67") (pin "1") (pinfunction "1_1") (pintype "passive"))
      (node (ref "R74") (pin "2") (pinfunction "2_2") (pintype "passive"))
    )
    (net (code "146") (name "VCM2") (class "Default")
      (node (ref "C195") (pin "2") (pinfunction "2_2") (pintype "passive"))
      (node (ref "D15") (pin "15") (pinfunction "VCM2_15") (pintype "passive"))
      (node (ref "R82") (pin "1") (pinfunction "1_1") (pintype "passive"))
      (node (ref "R83") (pin "1") (pinfunction "1_1") (pintype "passive"))
      (node (ref "R89") (pin "2") (pinfunction "2_2") (pintype "passive"))
    )
    (net (code "147") (name "unconnected-(D7E-IO_L12N_T1_MRCC_33-PadY7)") (class "Default")
      (node (ref "D7") (pin "Y7") (pinfunction "IO_L12N_T1_MRCC_33_Y7") (pintype "bidirectional"))
    )
    (net (code "148") (name "unconnected-(D7E-IO_L12P_T1_MRCC_33-PadY8)") (class "Default")
      (node (ref "D7") (pin "Y8") (pinfunction "IO_L12P_T1_MRCC_33_Y8") (pintype "bidirectional"))
    )
    (net (code "149") (name "unconnected-(D7E-IO_L21N_T3_DQS_33-PadAA13)") (class "Default")
      (node (ref "D7") (pin "AA13") (pinfunction "IO_L21N_T3_DQS_33_AA13") (pintype "bidirectional"))
    )
    (net (code "150") (name "unconnected-(D7E-IO_L21P_T3_DQS_33-PadY13)") (class "Default")
      (node (ref "D7") (pin "Y13") (pinfunction "IO_L21P_T3_DQS_33_Y13") (pintype "bidirectional"))
    )
    (net (code "151") (name "unconnected-(D7E-IO_L24P_T3_33-PadT13)") (class "Default")
      (node (ref "D7") (pin "T13") (pinfunction "IO_L24P_T3_33_T13") (pintype "bidirectional"))
    )
    (net (code "152") (name "unconnected-(D7F-IO_25_VRP_33-PadT14)") (class "Default")
      (node (ref "D7") (pin "T14") (pinfunction "IO_25_VRP_33_T14") (pintype "bidirectional"))
    )
    (net (code "153") (name "unconnected-(D7F-IO_L7N_T1_34-PadR2)") (class "Default")
      (node (ref "D7") (pin "R2") (pinfunction "IO_L7N_T1_34_R2") (pintype "bidirectional"))
    )
    (net (code "154") (name "unconnected-(D7F-IO_L7P_T1_34-PadP2)") (class "Default")
      (node (ref "D7") (pin "P2") (pinfunction "IO_L7P_T1_34_P2") (pintype "bidirectional"))
    )
    (net (code "155") (name "unconnected-(D7F-IO_L13N_T2_MRCC_34-PadU3)") (class "Default")
      (node (ref "D7") (pin "U3") (pinfunction "IO_L13N_T2_MRCC_34_U3") (pintype "bidirectional"))
    )
    (net (code "156") (name "unconnected-(D7F-IO_L13P_T2_MRCC_34-PadT4)") (class "Default")
      (node (ref "D7") (pin "T4") (pinfunction "IO_L13P_T2_MRCC_34_T4") (pintype "bidirectional"))
    )
    (net (code "157") (name "unconnected-(D7F-IO_L16N_T2_34-PadU5)") (class "Default")
      (node (ref "D7") (pin "U5") (pinfunction "IO_L16N_T2_34_U5") (pintype "bidirectional"))
    )
    (net (code "158") (name "unconnected-(D7F-IO_L16P_T2_34-PadT5)") (class "Default")
      (node (ref "D7") (pin "T5") (pinfunction "IO_L16P_T2_34_T5") (pintype "bidirectional"))
    )
    (net (code "159") (name "unconnected-(D7F-IO_L17N_T2_34-PadW2)") (class "Default")
      (node (ref "D7") (pin "W2") (pinfunction "IO_L17N_T2_34_W2") (pintype "bidirectional"))
    )
    (net (code "160") (name "unconnected-(D7F-IO_L17P_T2_34-PadV3)") (class "Default")
      (node (ref "D7") (pin "V3") (pinfunction "IO_L17P_T2_34_V3") (pintype "bidirectional"))
    )
    (net (code "161") (name "unconnected-(D7F-IO_L23P_T3_34-PadAA3)") (class "Default")
      (node (ref "D7") (pin "AA3") (pinfunction "IO_L23P_T3_34_AA3") (pintype "bidirectional"))
    )
    (net (code "162") (name "unconnected-(D16-~{SHDN}-Pad3)") (class "Default")
      (node (ref "D16") (pin "3") (pinfunction "~{SHDN}_3") (pintype "passive"))
    )
    (net (code "163") (name "unconnected-(D17-~{SHDN}-Pad3)") (class "Default")
      (node (ref "D17") (pin "3") (pinfunction "~{SHDN}_3") (pintype "passive"))
    )
    (net (code "164") (name "unconnected-(D19-SNS*-Pad6)") (class "Default")
      (node (ref "D19") (pin "6") (pinfunction "SNS*_6") (pintype "passive"))
    )
    (net (code "165") (name "unconnected-(D20-SNS*-Pad6)") (class "Default")
      (node (ref "D20") (pin "6") (pinfunction "SNS*_6") (pintype "passive"))
    )
    (net (code "166") (name "unconnected-(D21-SNS*-Pad6)") (class "Default")
      (node (ref "D21") (pin "6") (pinfunction "SNS*_6") (pintype "passive"))
    )
    (net (code "167") (name "unconnected-(D22-SNS*-Pad6)") (class "Default")
      (node (ref "D22") (pin "6") (pinfunction "SNS*_6") (pintype "passive"))
    )
  )
)
